# board.net
KiCad netlist of a schematic drawn in EAGLE
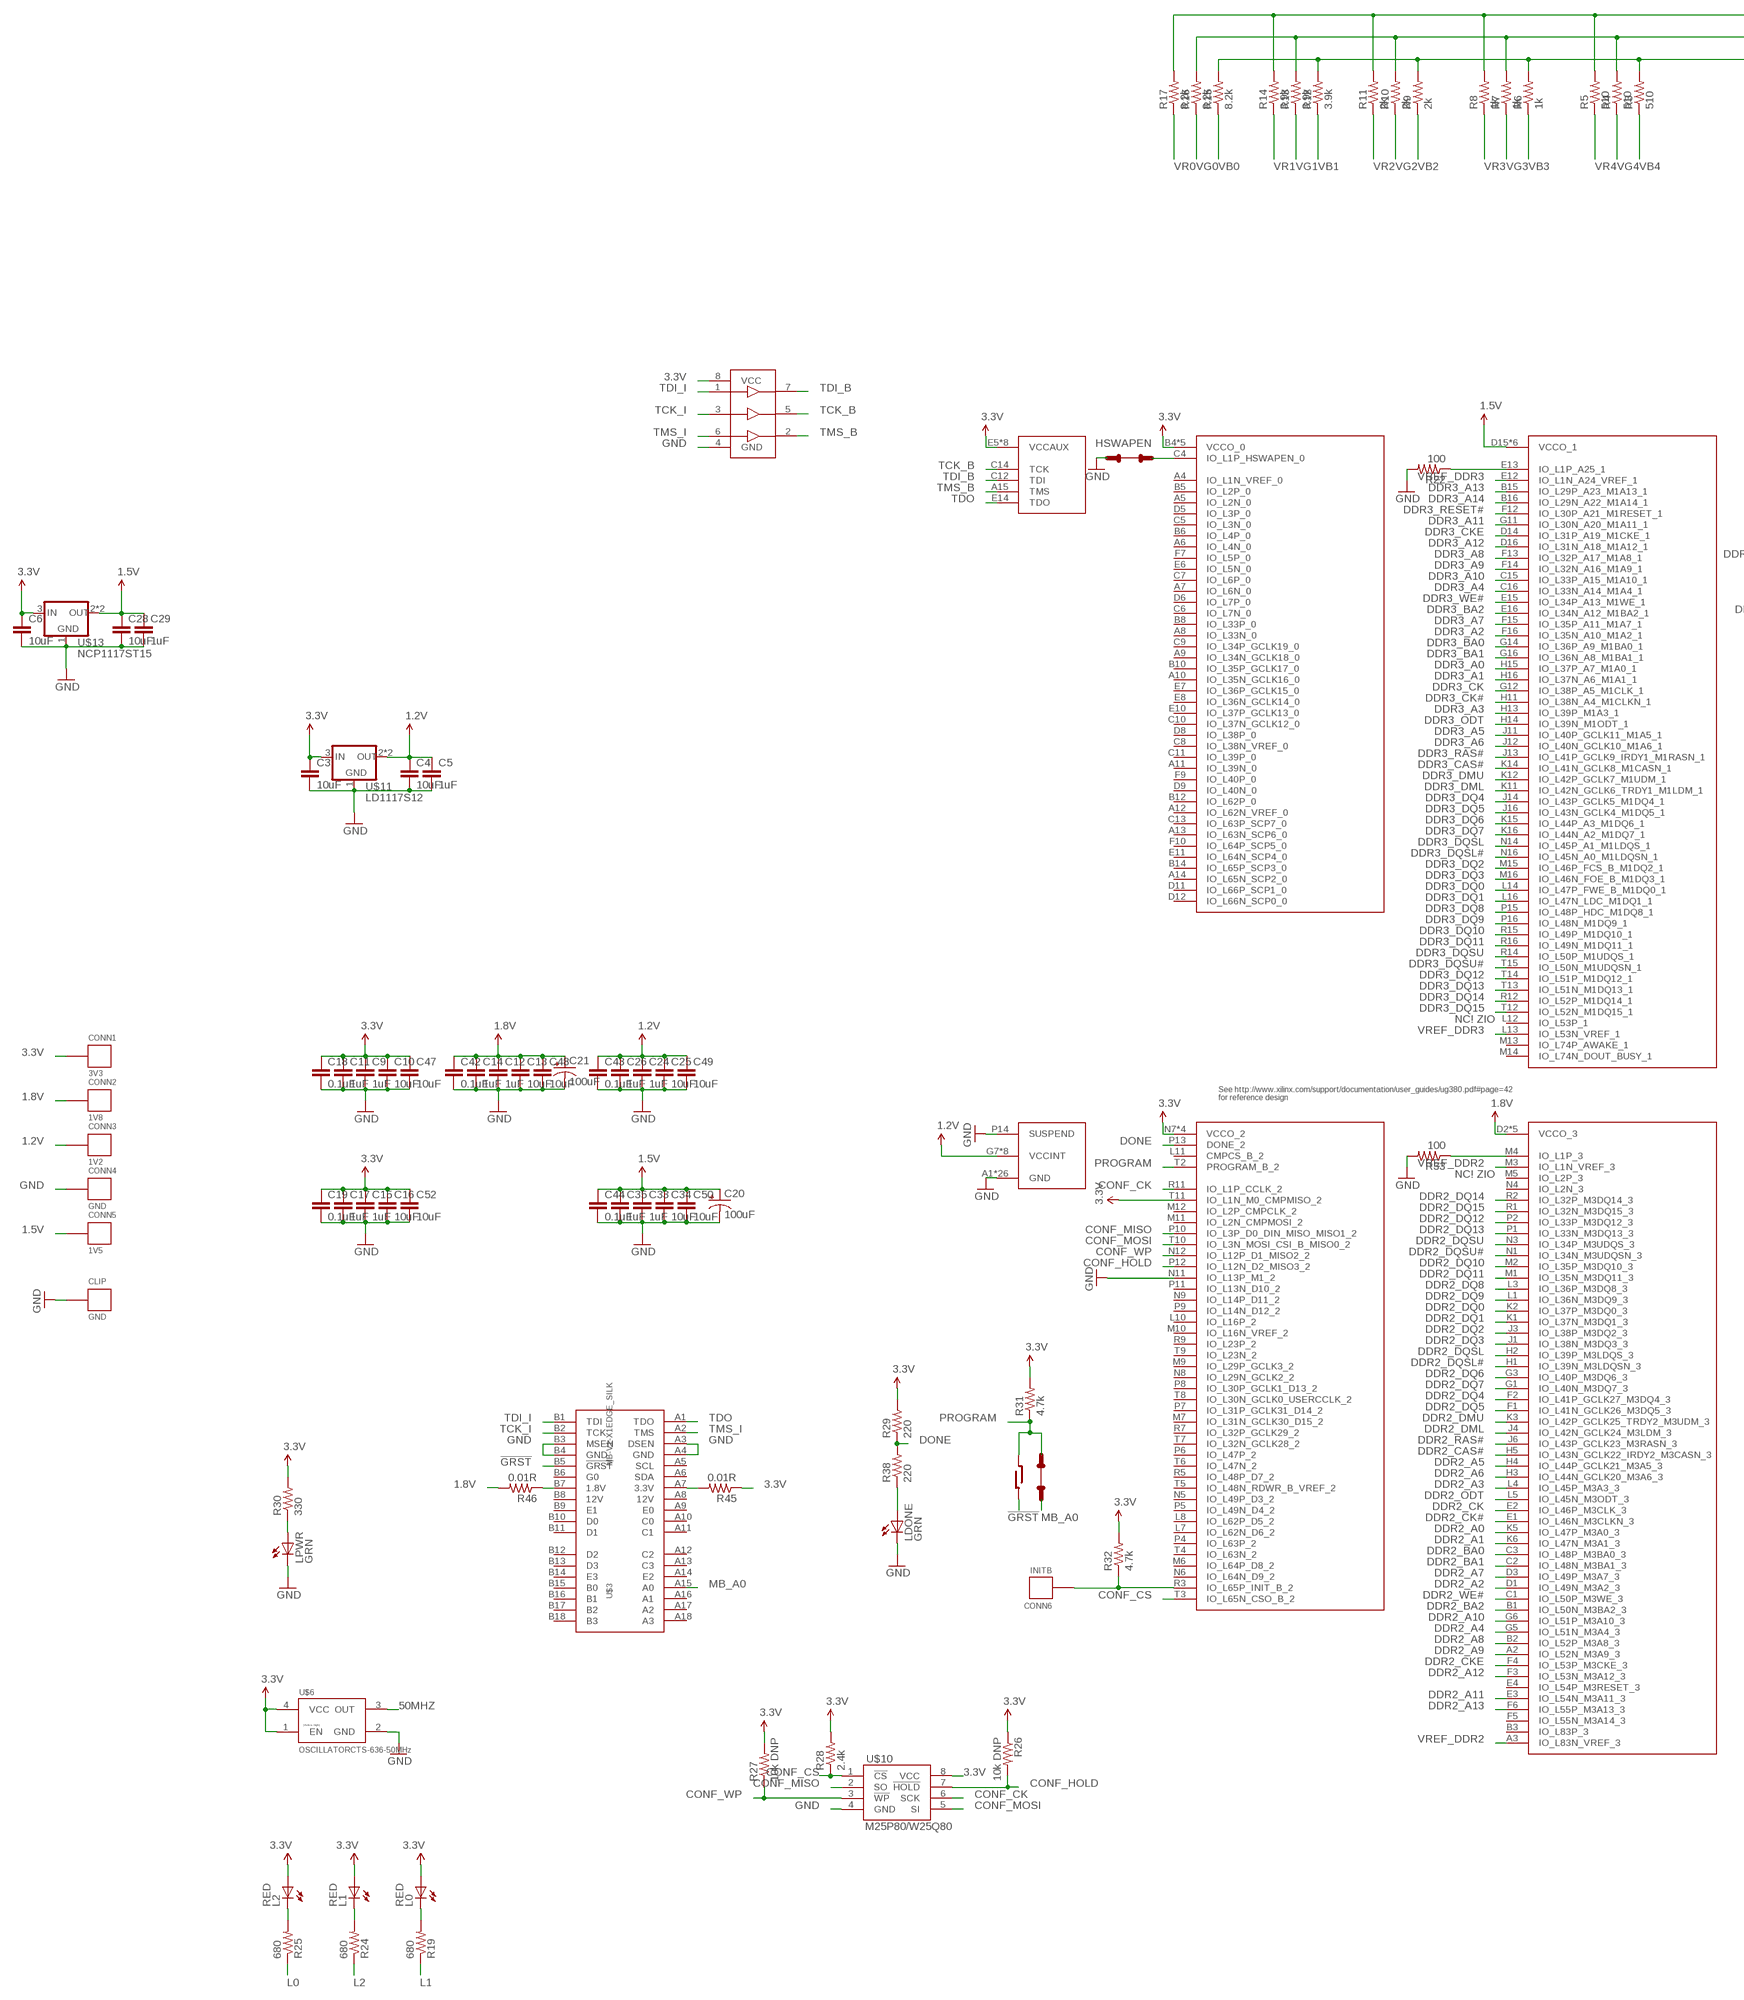
[diagram p0: schematic, sheet 1, part 1 of 2]
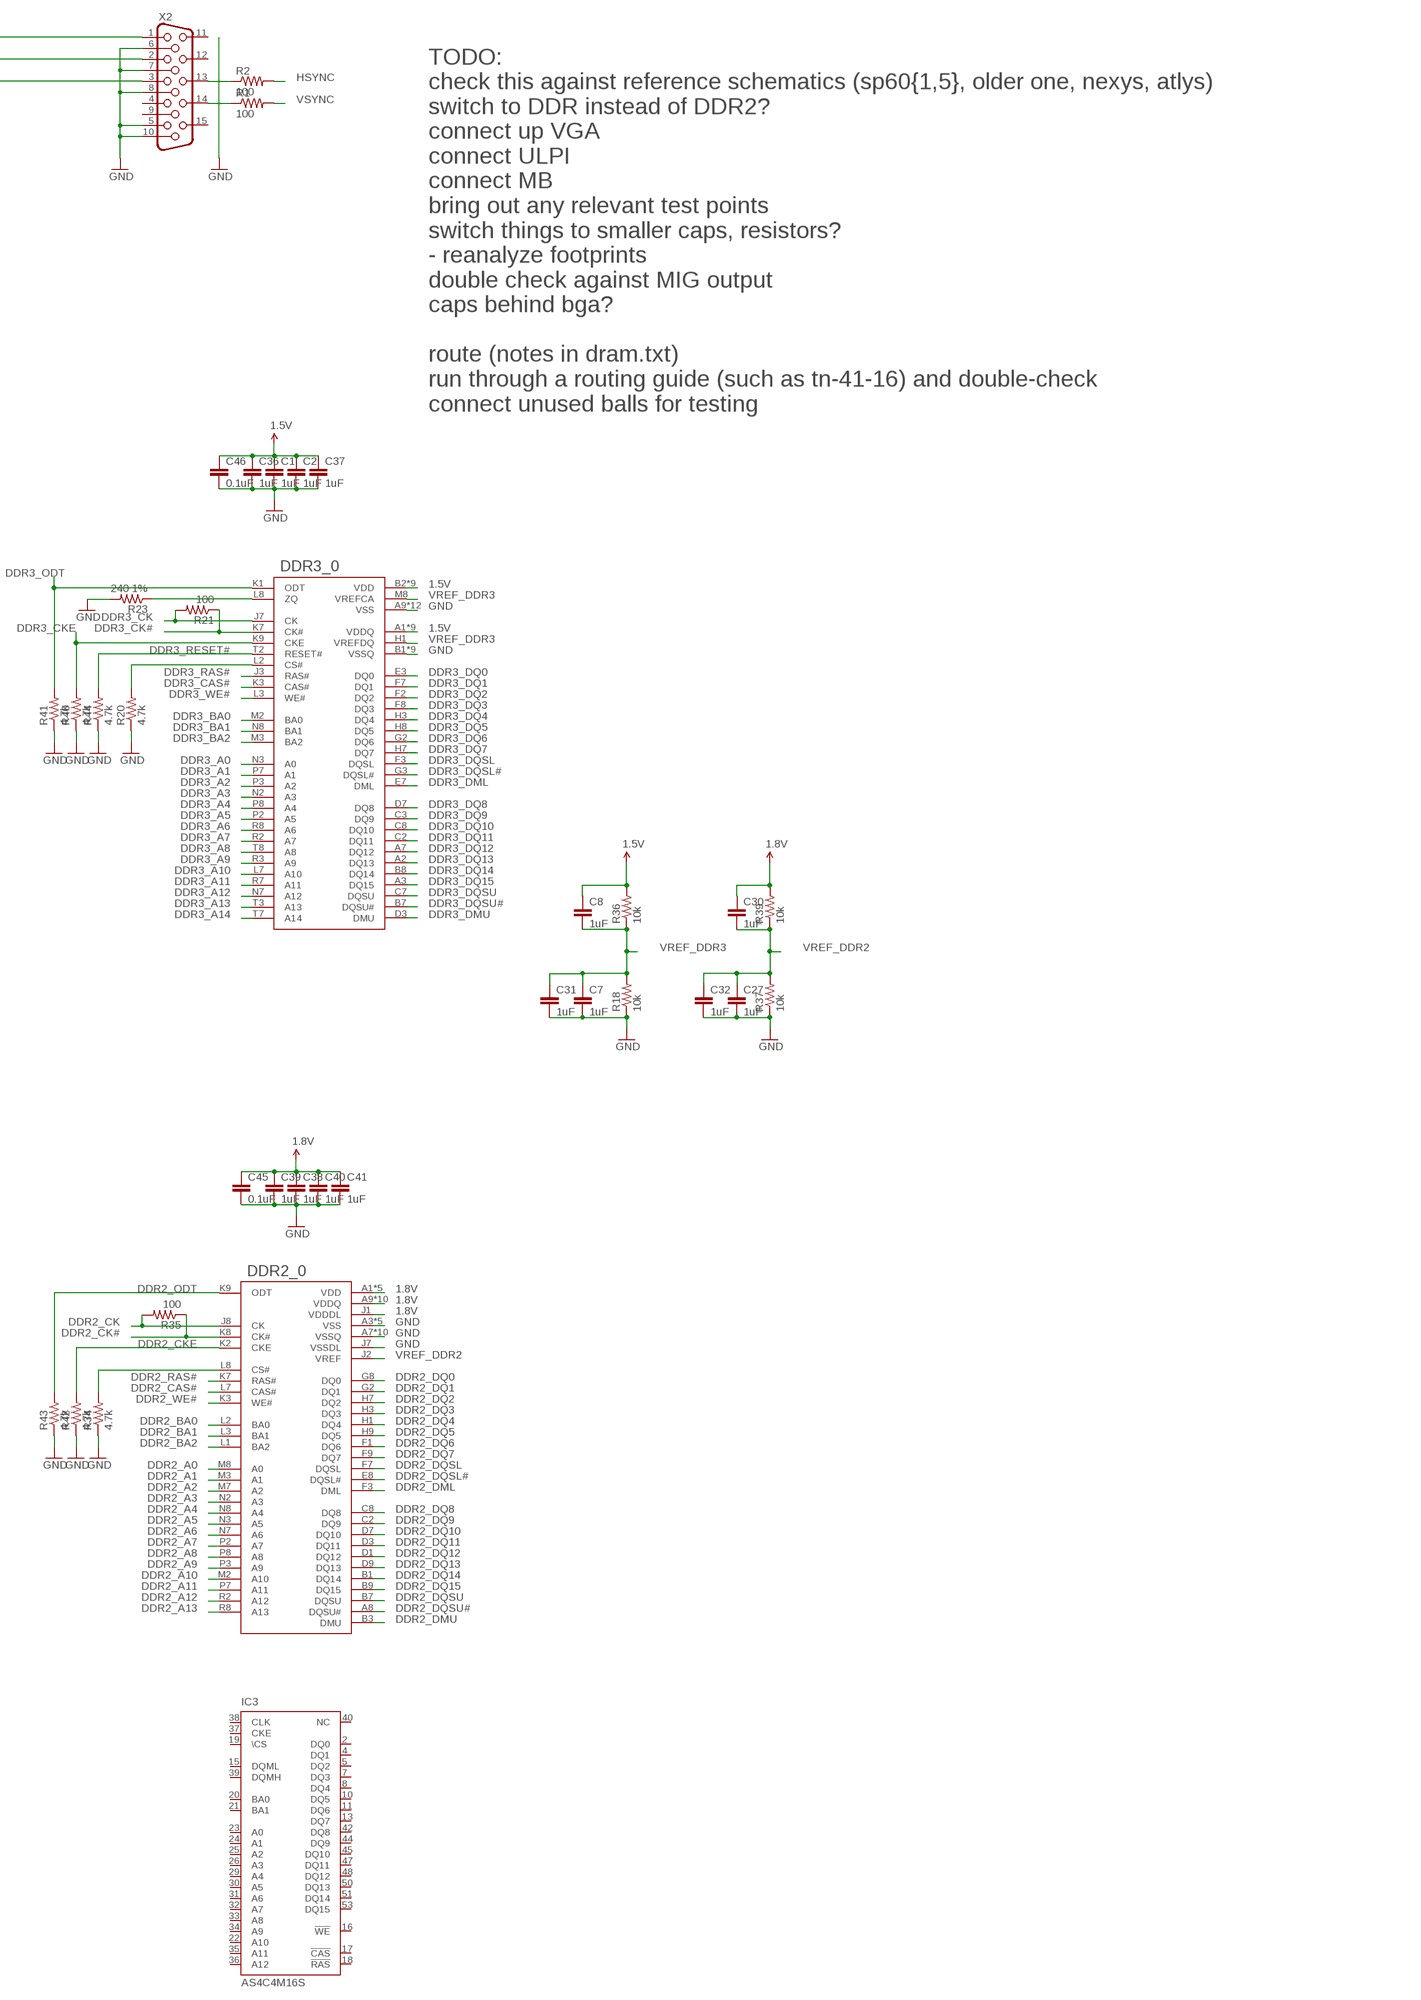
[diagram p1: schematic, sheet 1, part 2 of 2]

(export (version "E")
  (design (tool "Eeschema 10.0.6"))
  (components
    (comp (ref "C1")
      (value "1uF")
      (footprint "eagle-import:0402-CAP")
      (libsource (lib "eagle-import") (part "CAP0402-CAP"))
    )
    (comp (ref "C2")
      (value "1uF")
      (footprint "eagle-import:0402-CAP")
      (libsource (lib "eagle-import") (part "CAP0402-CAP"))
    )
    (comp (ref "C3")
      (value "10uF")
      (footprint "eagle-import:0603-CAP")
      (libsource (lib "eagle-import") (part "CAP0603"))
    )
    (comp (ref "C4")
      (value "10uF")
      (footprint "eagle-import:0603-CAP")
      (libsource (lib "eagle-import") (part "CAP0603"))
    )
    (comp (ref "C5")
      (value "1uF")
      (footprint "eagle-import:0402-CAP")
      (libsource (lib "eagle-import") (part "CAP0402-CAP"))
    )
    (comp (ref "C6")
      (value "10uF")
      (footprint "eagle-import:0603-CAP")
      (libsource (lib "eagle-import") (part "CAP0603"))
    )
    (comp (ref "C7")
      (value "1uF")
      (footprint "eagle-import:0402-CAP")
      (libsource (lib "eagle-import") (part "CAP0402-CAP"))
    )
    (comp (ref "C8")
      (value "1uF")
      (footprint "eagle-import:0402-CAP")
      (libsource (lib "eagle-import") (part "CAP0402-CAP"))
    )
    (comp (ref "C9")
      (value "1uF")
      (footprint "eagle-import:0402-CAP")
      (libsource (lib "eagle-import") (part "CAP0402-CAP"))
    )
    (comp (ref "C10")
      (value "10uF")
      (footprint "eagle-import:0603-CAP")
      (libsource (lib "eagle-import") (part "CAP0603"))
    )
    (comp (ref "C11")
      (value "1uF")
      (footprint "eagle-import:0402-CAP")
      (libsource (lib "eagle-import") (part "CAP0402-CAP"))
    )
    (comp (ref "C12")
      (value "1uF")
      (footprint "eagle-import:0402-CAP")
      (libsource (lib "eagle-import") (part "CAP0402-CAP"))
    )
    (comp (ref "C13")
      (value "10uF")
      (footprint "eagle-import:0603-CAP")
      (libsource (lib "eagle-import") (part "CAP0603"))
    )
    (comp (ref "C14")
      (value "1uF")
      (footprint "eagle-import:0402-CAP")
      (libsource (lib "eagle-import") (part "CAP0402-CAP"))
    )
    (comp (ref "C15")
      (value "1uF")
      (footprint "eagle-import:0402-CAP")
      (libsource (lib "eagle-import") (part "CAP0402-CAP"))
    )
    (comp (ref "C16")
      (value "10uF")
      (footprint "eagle-import:0603-CAP")
      (libsource (lib "eagle-import") (part "CAP0603"))
    )
    (comp (ref "C17")
      (value "1uF")
      (footprint "eagle-import:0402-CAP")
      (libsource (lib "eagle-import") (part "CAP0402-CAP"))
    )
    (comp (ref "C18")
      (value "0.1uF")
      (footprint "eagle-import:C0201")
      (libsource (lib "eagle-import") (part "CAP0201"))
    )
    (comp (ref "C19")
      (value "0.1uF")
      (footprint "eagle-import:C0201")
      (libsource (lib "eagle-import") (part "CAP0201"))
    )
    (comp (ref "C20")
      (value "100uF")
      (footprint "eagle-import:CAP-5-2")
      (libsource (lib "eagle-import") (part "CAP_POLPTH-5-2"))
    )
    (comp (ref "C21")
      (value "100uF")
      (footprint "eagle-import:CAP-5-2")
      (libsource (lib "eagle-import") (part "CAP_POLPTH-5-2"))
    )
    (comp (ref "C24")
      (value "1uF")
      (footprint "eagle-import:0402-CAP")
      (libsource (lib "eagle-import") (part "CAP0402-CAP"))
    )
    (comp (ref "C25")
      (value "10uF")
      (footprint "eagle-import:0603-CAP")
      (libsource (lib "eagle-import") (part "CAP0603"))
    )
    (comp (ref "C26")
      (value "1uF")
      (footprint "eagle-import:0402-CAP")
      (libsource (lib "eagle-import") (part "CAP0402-CAP"))
    )
    (comp (ref "C27")
      (value "1uF")
      (footprint "eagle-import:0402-CAP")
      (libsource (lib "eagle-import") (part "CAP0402-CAP"))
    )
    (comp (ref "C28")
      (value "10uF")
      (footprint "eagle-import:0603-CAP")
      (libsource (lib "eagle-import") (part "CAP0603"))
    )
    (comp (ref "C29")
      (value "1uF")
      (footprint "eagle-import:0402-CAP")
      (libsource (lib "eagle-import") (part "CAP0402-CAP"))
    )
    (comp (ref "C30")
      (value "1uF")
      (footprint "eagle-import:0402-CAP")
      (libsource (lib "eagle-import") (part "CAP0402-CAP"))
    )
    (comp (ref "C31")
      (value "1uF")
      (footprint "eagle-import:0402-CAP")
      (libsource (lib "eagle-import") (part "CAP0402-CAP"))
    )
    (comp (ref "C32")
      (value "1uF")
      (footprint "eagle-import:0402-CAP")
      (libsource (lib "eagle-import") (part "CAP0402-CAP"))
    )
    (comp (ref "C33")
      (value "1uF")
      (footprint "eagle-import:0402-CAP")
      (libsource (lib "eagle-import") (part "CAP0402-CAP"))
    )
    (comp (ref "C34")
      (value "10uF")
      (footprint "eagle-import:0603-CAP")
      (libsource (lib "eagle-import") (part "CAP0603"))
    )
    (comp (ref "C35")
      (value "1uF")
      (footprint "eagle-import:0402-CAP")
      (libsource (lib "eagle-import") (part "CAP0402-CAP"))
    )
    (comp (ref "C36")
      (value "1uF")
      (footprint "eagle-import:0402-CAP")
      (libsource (lib "eagle-import") (part "CAP0402-CAP"))
    )
    (comp (ref "C37")
      (value "1uF")
      (footprint "eagle-import:0402-CAP")
      (libsource (lib "eagle-import") (part "CAP0402-CAP"))
    )
    (comp (ref "C38")
      (value "1uF")
      (footprint "eagle-import:0402-CAP")
      (libsource (lib "eagle-import") (part "CAP0402-CAP"))
    )
    (comp (ref "C39")
      (value "1uF")
      (footprint "eagle-import:0402-CAP")
      (libsource (lib "eagle-import") (part "CAP0402-CAP"))
    )
    (comp (ref "C40")
      (value "1uF")
      (footprint "eagle-import:0402-CAP")
      (libsource (lib "eagle-import") (part "CAP0402-CAP"))
    )
    (comp (ref "C41")
      (value "1uF")
      (footprint "eagle-import:0402-CAP")
      (libsource (lib "eagle-import") (part "CAP0402-CAP"))
    )
    (comp (ref "C42")
      (value "0.1uF")
      (footprint "eagle-import:C0201")
      (libsource (lib "eagle-import") (part "CAP0201"))
    )
    (comp (ref "C43")
      (value "0.1uF")
      (footprint "eagle-import:C0201")
      (libsource (lib "eagle-import") (part "CAP0201"))
    )
    (comp (ref "C44")
      (value "0.1uF")
      (footprint "eagle-import:C0201")
      (libsource (lib "eagle-import") (part "CAP0201"))
    )
    (comp (ref "C45")
      (value "0.1uF")
      (footprint "eagle-import:C0201")
      (libsource (lib "eagle-import") (part "CAP0201"))
    )
    (comp (ref "C46")
      (value "0.1uF")
      (footprint "eagle-import:C0201")
      (libsource (lib "eagle-import") (part "CAP0201"))
    )
    (comp (ref "C47")
      (value "10uF")
      (footprint "eagle-import:0603-CAP")
      (libsource (lib "eagle-import") (part "CAP0603"))
    )
    (comp (ref "C48")
      (value "10uF")
      (footprint "eagle-import:0603-CAP")
      (libsource (lib "eagle-import") (part "CAP0603"))
    )
    (comp (ref "C49")
      (value "10uF")
      (footprint "eagle-import:0603-CAP")
      (libsource (lib "eagle-import") (part "CAP0603"))
    )
    (comp (ref "C50")
      (value "10uF")
      (footprint "eagle-import:0603-CAP")
      (libsource (lib "eagle-import") (part "CAP0603"))
    )
    (comp (ref "C52")
      (value "10uF")
      (footprint "eagle-import:0603-CAP")
      (libsource (lib "eagle-import") (part "CAP0603"))
    )
    (comp (ref "CLIP")
      (value "GND")
      (footprint "eagle-import:CLIP-AREA")
      (libsource (lib "eagle-import") (part "CONNECTORCLIP"))
    )
    (comp (ref "CONN1")
      (value "3V3")
      (footprint "eagle-import:HOLE_22AWG")
      (libsource (lib "eagle-import") (part "CONNECTOR22AWG"))
    )
    (comp (ref "CONN2")
      (value "1V8")
      (footprint "eagle-import:HOLE_22AWG")
      (libsource (lib "eagle-import") (part "CONNECTOR22AWG"))
    )
    (comp (ref "CONN3")
      (value "1V2")
      (footprint "eagle-import:HOLE_22AWG")
      (libsource (lib "eagle-import") (part "CONNECTOR22AWG"))
    )
    (comp (ref "CONN4")
      (value "GND")
      (footprint "eagle-import:HOLE_22AWG")
      (libsource (lib "eagle-import") (part "CONNECTOR22AWG"))
    )
    (comp (ref "CONN5")
      (value "1V5")
      (footprint "eagle-import:HOLE_22AWG")
      (libsource (lib "eagle-import") (part "CONNECTOR22AWG"))
    )
    (comp (ref "CONN6")
      (value "INITB")
      (footprint "eagle-import:TESTPAD-1.27")
      (libsource (lib "eagle-import") (part "CONNECTOR1.27"))
    )
    (comp (ref "DDR2_0")
      (value "DDR2X16")
      (footprint "eagle-import:BGA84")
      (libsource (lib "eagle-import") (part "DDR2X16"))
    )
    (comp (ref "DDR3_0")
      (value "DDR3X16")
      (footprint "eagle-import:BGA96")
      (libsource (lib "eagle-import") (part "DDR3X16"))
    )
    (comp (ref "IC1")
      (value "XC6S{9,16,25}LX-FT256")
      (footprint "eagle-import:XILINX_FT256")
      (libsource (lib "eagle-import") (part "XC6S{9,16,25}LX-FT256"))
    )
    (comp (ref "IC2")
      (value "74X3G34")
      (footprint "eagle-import:TSSOP8")
      (libsource (lib "eagle-import") (part "74X3G34"))
    )
    (comp (ref "IC3")
      (value "AS4C4M16S")
      (footprint "eagle-import:TSOP54-400")
      (libsource (lib "eagle-import") (part "MT48LC64M4A2"))
    )
    (comp (ref "L0")
      (value "RED")
      (footprint "eagle-import:0603_LED")
      (libsource (lib "eagle-import") (part "LED0603"))
    )
    (comp (ref "L1")
      (value "RED")
      (footprint "eagle-import:0603_LED")
      (libsource (lib "eagle-import") (part "LED0603"))
    )
    (comp (ref "L2")
      (value "RED")
      (footprint "eagle-import:0603_LED")
      (libsource (lib "eagle-import") (part "LED0603"))
    )
    (comp (ref "LDONE")
      (value "GRN")
      (footprint "eagle-import:0603_LED")
      (libsource (lib "eagle-import") (part "LED0603"))
    )
    (comp (ref "LPWR")
      (value "GRN")
      (footprint "eagle-import:0603_LED")
      (libsource (lib "eagle-import") (part "LED0603"))
    )
    (comp (ref "R1")
      (value "100")
      (footprint "eagle-import:0603-RES")
      (libsource (lib "eagle-import") (part "RESISTOR0603"))
    )
    (comp (ref "R2")
      (value "100")
      (footprint "eagle-import:0603-RES")
      (libsource (lib "eagle-import") (part "RESISTOR0603"))
    )
    (comp (ref "R3")
      (value "510")
      (footprint "eagle-import:0603-RES")
      (libsource (lib "eagle-import") (part "RESISTOR0603"))
    )
    (comp (ref "R4")
      (value "510")
      (footprint "eagle-import:0603-RES")
      (libsource (lib "eagle-import") (part "RESISTOR0603"))
    )
    (comp (ref "R5")
      (value "510")
      (footprint "eagle-import:0603-RES")
      (libsource (lib "eagle-import") (part "RESISTOR0603"))
    )
    (comp (ref "R6")
      (value "1k")
      (footprint "eagle-import:0603-RES")
      (libsource (lib "eagle-import") (part "RESISTOR0603"))
    )
    (comp (ref "R7")
      (value "1k")
      (footprint "eagle-import:0603-RES")
      (libsource (lib "eagle-import") (part "RESISTOR0603"))
    )
    (comp (ref "R8")
      (value "1k")
      (footprint "eagle-import:0603-RES")
      (libsource (lib "eagle-import") (part "RESISTOR0603"))
    )
    (comp (ref "R9")
      (value "2k")
      (footprint "eagle-import:0603-RES")
      (libsource (lib "eagle-import") (part "RESISTOR0603"))
    )
    (comp (ref "R10")
      (value "2k")
      (footprint "eagle-import:0603-RES")
      (libsource (lib "eagle-import") (part "RESISTOR0603"))
    )
    (comp (ref "R11")
      (value "2k")
      (footprint "eagle-import:0603-RES")
      (libsource (lib "eagle-import") (part "RESISTOR0603"))
    )
    (comp (ref "R12")
      (value "3.9k")
      (footprint "eagle-import:0603-RES")
      (libsource (lib "eagle-import") (part "RESISTOR0603"))
    )
    (comp (ref "R13")
      (value "3.9k")
      (footprint "eagle-import:0603-RES")
      (libsource (lib "eagle-import") (part "RESISTOR0603"))
    )
    (comp (ref "R14")
      (value "3.9k")
      (footprint "eagle-import:0603-RES")
      (libsource (lib "eagle-import") (part "RESISTOR0603"))
    )
    (comp (ref "R15")
      (value "8.2k")
      (footprint "eagle-import:0603-RES")
      (libsource (lib "eagle-import") (part "RESISTOR0603"))
    )
    (comp (ref "R16")
      (value "8.2k")
      (footprint "eagle-import:0603-RES")
      (libsource (lib "eagle-import") (part "RESISTOR0603"))
    )
    (comp (ref "R17")
      (value "8.2k")
      (footprint "eagle-import:0603-RES")
      (libsource (lib "eagle-import") (part "RESISTOR0603"))
    )
    (comp (ref "R18")
      (value "10k")
      (footprint "eagle-import:0603-RES")
      (libsource (lib "eagle-import") (part "RESISTOR0603"))
    )
    (comp (ref "R19")
      (value "680")
      (footprint "eagle-import:0603-RES")
      (libsource (lib "eagle-import") (part "RESISTOR0603"))
    )
    (comp (ref "R20")
      (value "4.7k")
      (footprint "eagle-import:0402-RES")
      (libsource (lib "eagle-import") (part "RESISTOR0402"))
    )
    (comp (ref "R21")
      (value "100")
      (footprint "eagle-import:0603-RES")
      (libsource (lib "eagle-import") (part "RESISTOR0603"))
    )
    (comp (ref "R22")
      (value "100")
      (footprint "eagle-import:0603-RES")
      (libsource (lib "eagle-import") (part "RESISTOR0603"))
    )
    (comp (ref "R23")
      (value "240 1%")
      (footprint "eagle-import:0603-RES")
      (libsource (lib "eagle-import") (part "RESISTOR0603"))
    )
    (comp (ref "R24")
      (value "680")
      (footprint "eagle-import:0603-RES")
      (libsource (lib "eagle-import") (part "RESISTOR0603"))
    )
    (comp (ref "R25")
      (value "680")
      (footprint "eagle-import:0603-RES")
      (libsource (lib "eagle-import") (part "RESISTOR0603"))
    )
    (comp (ref "R26")
      (value "10k DNP")
      (footprint "eagle-import:0402-RES")
      (libsource (lib "eagle-import") (part "RESISTOR0402"))
    )
    (comp (ref "R27")
      (value "10k DNP")
      (footprint "eagle-import:0402-RES")
      (libsource (lib "eagle-import") (part "RESISTOR0402"))
    )
    (comp (ref "R28")
      (value "2.4k")
      (footprint "eagle-import:0603-RES")
      (libsource (lib "eagle-import") (part "RESISTOR0603"))
    )
    (comp (ref "R29")
      (value "220")
      (footprint "eagle-import:0603-RES")
      (libsource (lib "eagle-import") (part "RESISTOR0603"))
    )
    (comp (ref "R30")
      (value "330")
      (footprint "eagle-import:0603-RES")
      (libsource (lib "eagle-import") (part "RESISTOR0603"))
    )
    (comp (ref "R31")
      (value "4.7k")
      (footprint "eagle-import:0603-RES")
      (libsource (lib "eagle-import") (part "RESISTOR0603"))
    )
    (comp (ref "R32")
      (value "4.7k")
      (footprint "eagle-import:0603-RES")
      (libsource (lib "eagle-import") (part "RESISTOR0603"))
    )
    (comp (ref "R33")
      (value "100")
      (footprint "eagle-import:0603-RES")
      (libsource (lib "eagle-import") (part "RESISTOR0603"))
    )
    (comp (ref "R34")
      (value "4.7k")
      (footprint "eagle-import:0402-RES")
      (libsource (lib "eagle-import") (part "RESISTOR0402"))
    )
    (comp (ref "R35")
      (value "100")
      (footprint "eagle-import:0603-RES")
      (libsource (lib "eagle-import") (part "RESISTOR0603"))
    )
    (comp (ref "R36")
      (value "10k")
      (footprint "eagle-import:0603-RES")
      (libsource (lib "eagle-import") (part "RESISTOR0603"))
    )
    (comp (ref "R37")
      (value "10k")
      (footprint "eagle-import:0603-RES")
      (libsource (lib "eagle-import") (part "RESISTOR0603"))
    )
    (comp (ref "R38")
      (value "220")
      (footprint "eagle-import:0603-RES")
      (libsource (lib "eagle-import") (part "RESISTOR0603"))
    )
    (comp (ref "R39")
      (value "10k")
      (footprint "eagle-import:0603-RES")
      (libsource (lib "eagle-import") (part "RESISTOR0603"))
    )
    (comp (ref "R40")
      (value "4.7k")
      (footprint "eagle-import:0402-RES")
      (libsource (lib "eagle-import") (part "RESISTOR0402"))
    )
    (comp (ref "R41")
      (value "4.7k")
      (footprint "eagle-import:0402-RES")
      (libsource (lib "eagle-import") (part "RESISTOR0402"))
    )
    (comp (ref "R42")
      (value "4.7k")
      (footprint "eagle-import:0402-RES")
      (libsource (lib "eagle-import") (part "RESISTOR0402"))
    )
    (comp (ref "R43")
      (value "4.7k")
      (footprint "eagle-import:0402-RES")
      (libsource (lib "eagle-import") (part "RESISTOR0402"))
    )
    (comp (ref "R44")
      (value "4.7k")
      (footprint "eagle-import:0402-RES")
      (libsource (lib "eagle-import") (part "RESISTOR0402"))
    )
    (comp (ref "R45")
      (value "0.01R")
      (footprint "eagle-import:0603-RES")
      (libsource (lib "eagle-import") (part "RESISTOR0603"))
    )
    (comp (ref "R46")
      (value "0.01R")
      (footprint "eagle-import:0603-RES")
      (libsource (lib "eagle-import") (part "RESISTOR0603"))
    )
    (comp (ref "SB1")
      (value "SOLDER-BRIDGEOPEN")
      (footprint "eagle-import:SOLDER-BRIDGE-OPEN")
      (libsource (lib "eagle-import") (part "SOLDER-BRIDGEOPEN"))
    )
    (comp (ref "SB2")
      (value "TRACE-CUT")
      (footprint "eagle-import:TRACE-CUT")
      (libsource (lib "eagle-import") (part "TRACE-CUT"))
    )
    (comp (ref "SB5")
      (value "TRACE-CUT")
      (footprint "eagle-import:TRACE-CUT")
      (libsource (lib "eagle-import") (part "TRACE-CUT"))
    )
    (comp (ref "U$3")
      (value "MB-V1-X1EDGE_SILK")
      (footprint "eagle-import:MB-V1-X1-EDGE")
      (libsource (lib "eagle-import") (part "MB-V1-X1EDGE_SILK"))
    )
    (comp (ref "U$6")
      (value "OSCILLATORCTS-636-50MHz")
      (footprint "eagle-import:CTS-636")
      (libsource (lib "eagle-import") (part "OSCILLATORCTS-636"))
    )
    (comp (ref "U$10")
      (value "M25P80/W25Q80")
      (footprint "eagle-import:SO08")
      (libsource (lib "eagle-import") (part "S25FL"))
    )
    (comp (ref "U$11")
      (value "LD1117S12")
      (footprint "eagle-import:SOT223")
      (libsource (lib "eagle-import") (part "VREGSOT223"))
    )
    (comp (ref "U$13")
      (value "NCP1117ST15")
      (footprint "eagle-import:SOT223")
      (libsource (lib "eagle-import") (part "VREGSOT223"))
    )
    (comp (ref "X2")
      (value "HF15H")
      (footprint "eagle-import:HDF15H")
      (libsource (lib "eagle-import") (part "HF15H"))
    )
  )
  (nets
    (net (code "1") (name "/50MHZ") (class "Default")
      (node (ref "U$6") (pin "3") (pinfunction "OUT_3") (pintype "bidirectional"))
    )
    (net (code "2") (name "/CONF_CK") (class "Default")
      (node (ref "IC1") (pin "R11") (pinfunction "IO_L1P_CCLK_2_R11") (pintype "bidirectional"))
      (node (ref "U$10") (pin "6") (pinfunction "SCK_6") (pintype "bidirectional"))
    )
    (net (code "3") (name "/CONF_CS") (class "Default")
      (node (ref "IC1") (pin "T3") (pinfunction "IO_L65N_CSO_B_2_T3") (pintype "bidirectional"))
      (node (ref "R28") (pin "1") (pinfunction "1_1") (pintype "passive"))
      (node (ref "U$10") (pin "1") (pinfunction "~{CS}_1") (pintype "bidirectional"))
    )
    (net (code "4") (name "/CONF_HOLD") (class "Default")
      (node (ref "IC1") (pin "P12") (pinfunction "IO_L12N_D2_MISO3_2_P12") (pintype "bidirectional"))
      (node (ref "R26") (pin "2") (pinfunction "2_2") (pintype "passive"))
      (node (ref "U$10") (pin "7") (pinfunction "~{HOLD}_7") (pintype "bidirectional"))
    )
    (net (code "5") (name "/CONF_MISO") (class "Default")
      (node (ref "IC1") (pin "P10") (pinfunction "IO_L3P_D0_DIN_MISO_MISO1_2_P10") (pintype "bidirectional"))
      (node (ref "U$10") (pin "2") (pinfunction "SO_2") (pintype "bidirectional"))
    )
    (net (code "6") (name "/CONF_MOSI") (class "Default")
      (node (ref "IC1") (pin "T10") (pinfunction "IO_L3N_MOSI_CSI_B_MISO0_2_T10") (pintype "bidirectional"))
      (node (ref "U$10") (pin "5") (pinfunction "SI_5") (pintype "bidirectional"))
    )
    (net (code "7") (name "/CONF_WP") (class "Default")
      (node (ref "IC1") (pin "N12") (pinfunction "IO_L12P_D1_MISO2_2_N12") (pintype "bidirectional"))
      (node (ref "R27") (pin "1") (pinfunction "1_1") (pintype "passive"))
      (node (ref "U$10") (pin "3") (pinfunction "~{WP}_3") (pintype "bidirectional"))
    )
    (net (code "8") (name "/DDR2_A0") (class "Default")
      (node (ref "DDR2_0") (pin "M8") (pinfunction "A0_M8") (pintype "input"))
      (node (ref "IC1") (pin "K5") (pinfunction "IO_L47P_M3A0_3_K5") (pintype "bidirectional"))
    )
    (net (code "9") (name "/DDR2_A1") (class "Default")
      (node (ref "DDR2_0") (pin "M3") (pinfunction "A1_M3") (pintype "input"))
      (node (ref "IC1") (pin "K6") (pinfunction "IO_L47N_M3A1_3_K6") (pintype "bidirectional"))
    )
    (net (code "10") (name "/DDR2_A2") (class "Default")
      (node (ref "DDR2_0") (pin "M7") (pinfunction "A2_M7") (pintype "input"))
      (node (ref "IC1") (pin "D1") (pinfunction "IO_L49N_M3A2_3_D1") (pintype "bidirectional"))
    )
    (net (code "11") (name "/DDR2_A3") (class "Default")
      (node (ref "DDR2_0") (pin "N2") (pinfunction "A3_N2") (pintype "input"))
      (node (ref "IC1") (pin "L4") (pinfunction "IO_L45P_M3A3_3_L4") (pintype "bidirectional"))
    )
    (net (code "12") (name "/DDR2_A4") (class "Default")
      (node (ref "DDR2_0") (pin "N8") (pinfunction "A4_N8") (pintype "input"))
      (node (ref "IC1") (pin "G5") (pinfunction "IO_L51N_M3A4_3_G5") (pintype "bidirectional"))
    )
    (net (code "13") (name "/DDR2_A5") (class "Default")
      (node (ref "DDR2_0") (pin "N3") (pinfunction "A5_N3") (pintype "input"))
      (node (ref "IC1") (pin "H4") (pinfunction "IO_L44P_GCLK21_M3A5_3_H4") (pintype "bidirectional"))
    )
    (net (code "14") (name "/DDR2_A6") (class "Default")
      (node (ref "DDR2_0") (pin "N7") (pinfunction "A6_N7") (pintype "input"))
      (node (ref "IC1") (pin "H3") (pinfunction "IO_L44N_GCLK20_M3A6_3_H3") (pintype "bidirectional"))
    )
    (net (code "15") (name "/DDR2_A7") (class "Default")
      (node (ref "DDR2_0") (pin "P2") (pinfunction "A7_P2") (pintype "input"))
      (node (ref "IC1") (pin "D3") (pinfunction "IO_L49P_M3A7_3_D3") (pintype "bidirectional"))
    )
    (net (code "16") (name "/DDR2_A8") (class "Default")
      (node (ref "DDR2_0") (pin "P8") (pinfunction "A8_P8") (pintype "input"))
      (node (ref "IC1") (pin "B2") (pinfunction "IO_L52P_M3A8_3_B2") (pintype "bidirectional"))
    )
    (net (code "17") (name "/DDR2_A9") (class "Default")
      (node (ref "DDR2_0") (pin "P3") (pinfunction "A9_P3") (pintype "input"))
      (node (ref "IC1") (pin "A2") (pinfunction "IO_L52N_M3A9_3_A2") (pintype "bidirectional"))
    )
    (net (code "18") (name "/DDR2_A10") (class "Default")
      (node (ref "DDR2_0") (pin "M2") (pinfunction "A10_M2") (pintype "input"))
      (node (ref "IC1") (pin "G6") (pinfunction "IO_L51P_M3A10_3_G6") (pintype "bidirectional"))
    )
    (net (code "19") (name "/DDR2_A11") (class "Default")
      (node (ref "DDR2_0") (pin "P7") (pinfunction "A11_P7") (pintype "input"))
      (node (ref "IC1") (pin "E3") (pinfunction "IO_L54N_M3A11_3_E3") (pintype "bidirectional"))
    )
    (net (code "20") (name "/DDR2_A12") (class "Default")
      (node (ref "DDR2_0") (pin "R2") (pinfunction "A12_R2") (pintype "input"))
      (node (ref "IC1") (pin "F3") (pinfunction "IO_L53N_M3A12_3_F3") (pintype "bidirectional"))
    )
    (net (code "21") (name "/DDR2_A13") (class "Default")
      (node (ref "DDR2_0") (pin "R8") (pinfunction "A13_R8") (pintype "input"))
      (node (ref "IC1") (pin "F6") (pinfunction "IO_L55P_M3A13_3_F6") (pintype "bidirectional"))
    )
    (net (code "22") (name "/DDR2_BA0") (class "Default")
      (node (ref "DDR2_0") (pin "L2") (pinfunction "BA0_L2") (pintype "input"))
      (node (ref "IC1") (pin "C3") (pinfunction "IO_L48P_M3BA0_3_C3") (pintype "bidirectional"))
    )
    (net (code "23") (name "/DDR2_BA1") (class "Default")
      (node (ref "DDR2_0") (pin "L3") (pinfunction "BA1_L3") (pintype "input"))
      (node (ref "IC1") (pin "C2") (pinfunction "IO_L48N_M3BA1_3_C2") (pintype "bidirectional"))
    )
    (net (code "24") (name "/DDR2_BA2") (class "Default")
      (node (ref "DDR2_0") (pin "L1") (pinfunction "BA2_L1") (pintype "input"))
      (node (ref "IC1") (pin "B1") (pinfunction "IO_L50N_M3BA2_3_B1") (pintype "bidirectional"))
    )
    (net (code "25") (name "/DDR2_CAS#") (class "Default")
      (node (ref "DDR2_0") (pin "L7") (pinfunction "CAS#_L7") (pintype "input"))
      (node (ref "IC1") (pin "H5") (pinfunction "IO_L43N_GCLK22_IRDY2_M3CASN_3_H5") (pintype "bidirectional"))
    )
    (net (code "26") (name "/DDR2_CK") (class "Default")
      (node (ref "DDR2_0") (pin "J8") (pinfunction "CK_J8") (pintype "input"))
      (node (ref "IC1") (pin "E2") (pinfunction "IO_L46P_M3CLK_3_E2") (pintype "bidirectional"))
      (node (ref "R35") (pin "2") (pinfunction "2_2") (pintype "passive"))
    )
    (net (code "27") (name "/DDR2_CK#") (class "Default")
      (node (ref "DDR2_0") (pin "K8") (pinfunction "CK#_K8") (pintype "input"))
      (node (ref "IC1") (pin "E1") (pinfunction "IO_L46N_M3CLKN_3_E1") (pintype "bidirectional"))
      (node (ref "R35") (pin "1") (pinfunction "1_1") (pintype "passive"))
    )
    (net (code "28") (name "/DDR2_CKE") (class "Default")
      (node (ref "DDR2_0") (pin "K2") (pinfunction "CKE_K2") (pintype "input"))
      (node (ref "IC1") (pin "F4") (pinfunction "IO_L53P_M3CKE_3_F4") (pintype "bidirectional"))
      (node (ref "R42") (pin "2") (pinfunction "2_2") (pintype "passive"))
    )
    (net (code "29") (name "/DDR2_DML") (class "Default")
      (node (ref "DDR2_0") (pin "F3") (pinfunction "DML_F3") (pintype "input"))
      (node (ref "IC1") (pin "J4") (pinfunction "IO_L42N_GCLK24_M3LDM_3_J4") (pintype "bidirectional"))
    )
    (net (code "30") (name "/DDR2_DMU") (class "Default")
      (node (ref "DDR2_0") (pin "B3") (pinfunction "DMU_B3") (pintype "input"))
      (node (ref "IC1") (pin "K3") (pinfunction "IO_L42P_GCLK25_TRDY2_M3UDM_3_K3") (pintype "bidirectional"))
    )
    (net (code "31") (name "/DDR2_DQ0") (class "Default")
      (node (ref "DDR2_0") (pin "G8") (pinfunction "DQ0_G8") (pintype "bidirectional"))
      (node (ref "IC1") (pin "K2") (pinfunction "IO_L37P_M3DQ0_3_K2") (pintype "bidirectional"))
    )
    (net (code "32") (name "/DDR2_DQ1") (class "Default")
      (node (ref "DDR2_0") (pin "G2") (pinfunction "DQ1_G2") (pintype "bidirectional"))
      (node (ref "IC1") (pin "K1") (pinfunction "IO_L37N_M3DQ1_3_K1") (pintype "bidirectional"))
    )
    (net (code "33") (name "/DDR2_DQ2") (class "Default")
      (node (ref "DDR2_0") (pin "H7") (pinfunction "DQ2_H7") (pintype "bidirectional"))
      (node (ref "IC1") (pin "J3") (pinfunction "IO_L38P_M3DQ2_3_J3") (pintype "bidirectional"))
    )
    (net (code "34") (name "/DDR2_DQ3") (class "Default")
      (node (ref "DDR2_0") (pin "H3") (pinfunction "DQ3_H3") (pintype "bidirectional"))
      (node (ref "IC1") (pin "J1") (pinfunction "IO_L38N_M3DQ3_3_J1") (pintype "bidirectional"))
    )
    (net (code "35") (name "/DDR2_DQ4") (class "Default")
      (node (ref "DDR2_0") (pin "H1") (pinfunction "DQ4_H1") (pintype "bidirectional"))
      (node (ref "IC1") (pin "F2") (pinfunction "IO_L41P_GCLK27_M3DQ4_3_F2") (pintype "bidirectional"))
    )
    (net (code "36") (name "/DDR2_DQ5") (class "Default")
      (node (ref "DDR2_0") (pin "H9") (pinfunction "DQ5_H9") (pintype "bidirectional"))
      (node (ref "IC1") (pin "F1") (pinfunction "IO_L41N_GCLK26_M3DQ5_3_F1") (pintype "bidirectional"))
    )
    (net (code "37") (name "/DDR2_DQ6") (class "Default")
      (node (ref "DDR2_0") (pin "F1") (pinfunction "DQ6_F1") (pintype "bidirectional"))
      (node (ref "IC1") (pin "G3") (pinfunction "IO_L40P_M3DQ6_3_G3") (pintype "bidirectional"))
    )
    (net (code "38") (name "/DDR2_DQ7") (class "Default")
      (node (ref "DDR2_0") (pin "F9") (pinfunction "DQ7_F9") (pintype "bidirectional"))
      (node (ref "IC1") (pin "G1") (pinfunction "IO_L40N_M3DQ7_3_G1") (pintype "bidirectional"))
    )
    (net (code "39") (name "/DDR2_DQ8") (class "Default")
      (node (ref "DDR2_0") (pin "C8") (pinfunction "DQ8_C8") (pintype "bidirectional"))
      (node (ref "IC1") (pin "L3") (pinfunction "IO_L36P_M3DQ8_3_L3") (pintype "bidirectional"))
    )
    (net (code "40") (name "/DDR2_DQ9") (class "Default")
      (node (ref "DDR2_0") (pin "C2") (pinfunction "DQ9_C2") (pintype "bidirectional"))
      (node (ref "IC1") (pin "L1") (pinfunction "IO_L36N_M3DQ9_3_L1") (pintype "bidirectional"))
    )
    (net (code "41") (name "/DDR2_DQ10") (class "Default")
      (node (ref "DDR2_0") (pin "D7") (pinfunction "DQ10_D7") (pintype "bidirectional"))
      (node (ref "IC1") (pin "M2") (pinfunction "IO_L35P_M3DQ10_3_M2") (pintype "bidirectional"))
    )
    (net (code "42") (name "/DDR2_DQ11") (class "Default")
      (node (ref "DDR2_0") (pin "D3") (pinfunction "DQ11_D3") (pintype "bidirectional"))
      (node (ref "IC1") (pin "M1") (pinfunction "IO_L35N_M3DQ11_3_M1") (pintype "bidirectional"))
    )
    (net (code "43") (name "/DDR2_DQ12") (class "Default")
      (node (ref "DDR2_0") (pin "D1") (pinfunction "DQ12_D1") (pintype "bidirectional"))
      (node (ref "IC1") (pin "P2") (pinfunction "IO_L33P_M3DQ12_3_P2") (pintype "bidirectional"))
    )
    (net (code "44") (name "/DDR2_DQ13") (class "Default")
      (node (ref "DDR2_0") (pin "D9") (pinfunction "DQ13_D9") (pintype "bidirectional"))
      (node (ref "IC1") (pin "P1") (pinfunction "IO_L33N_M3DQ13_3_P1") (pintype "bidirectional"))
    )
    (net (code "45") (name "/DDR2_DQ14") (class "Default")
      (node (ref "DDR2_0") (pin "B1") (pinfunction "DQ14_B1") (pintype "bidirectional"))
      (node (ref "IC1") (pin "R2") (pinfunction "IO_L32P_M3DQ14_3_R2") (pintype "bidirectional"))
    )
    (net (code "46") (name "/DDR2_DQ15") (class "Default")
      (node (ref "DDR2_0") (pin "B9") (pinfunction "DQ15_B9") (pintype "bidirectional"))
      (node (ref "IC1") (pin "R1") (pinfunction "IO_L32N_M3DQ15_3_R1") (pintype "bidirectional"))
    )
    (net (code "47") (name "/DDR2_DQSL") (class "Default")
      (node (ref "DDR2_0") (pin "F7") (pinfunction "DQSL_F7") (pintype "input"))
      (node (ref "IC1") (pin "H2") (pinfunction "IO_L39P_M3LDQS_3_H2") (pintype "bidirectional"))
    )
    (net (code "48") (name "/DDR2_DQSL#") (class "Default")
      (node (ref "DDR2_0") (pin "E8") (pinfunction "DQSL#_E8") (pintype "input"))
      (node (ref "IC1") (pin "H1") (pinfunction "IO_L39N_M3LDQSN_3_H1") (pintype "bidirectional"))
    )
    (net (code "49") (name "/DDR2_DQSU") (class "Default")
      (node (ref "DDR2_0") (pin "B7") (pinfunction "DQSU_B7") (pintype "input"))
      (node (ref "IC1") (pin "N3") (pinfunction "IO_L34P_M3UDQS_3_N3") (pintype "bidirectional"))
    )
    (net (code "50") (name "/DDR2_DQSU#") (class "Default")
      (node (ref "DDR2_0") (pin "A8") (pinfunction "DQSU#_A8") (pintype "input"))
      (node (ref "IC1") (pin "N1") (pinfunction "IO_L34N_M3UDQSN_3_N1") (pintype "bidirectional"))
    )
    (net (code "51") (name "/DDR2_ODT") (class "Default")
      (node (ref "DDR2_0") (pin "K9") (pinfunction "ODT_K9") (pintype "bidirectional"))
      (node (ref "IC1") (pin "L5") (pinfunction "IO_L45N_M3ODT_3_L5") (pintype "bidirectional"))
      (node (ref "R43") (pin "2") (pinfunction "2_2") (pintype "passive"))
    )
    (net (code "52") (name "/DDR2_RAS#") (class "Default")
      (node (ref "DDR2_0") (pin "K7") (pinfunction "RAS#_K7") (pintype "input"))
      (node (ref "IC1") (pin "J6") (pinfunction "IO_L43P_GCLK23_M3RASN_3_J6") (pintype "bidirectional"))
    )
    (net (code "53") (name "/DDR2_WE#") (class "Default")
      (node (ref "DDR2_0") (pin "K3") (pinfunction "WE#_K3") (pintype "input"))
      (node (ref "IC1") (pin "C1") (pinfunction "IO_L50P_M3WE_3_C1") (pintype "bidirectional"))
    )
    (net (code "54") (name "/DDR3_A0") (class "Default")
      (node (ref "DDR3_0") (pin "N3") (pinfunction "A0_N3") (pintype "input"))
      (node (ref "IC1") (pin "H15") (pinfunction "IO_L37P_A7_M1A0_1_H15") (pintype "bidirectional"))
    )
    (net (code "55") (name "/DDR3_A1") (class "Default")
      (node (ref "DDR3_0") (pin "P7") (pinfunction "A1_P7") (pintype "input"))
      (node (ref "IC1") (pin "H16") (pinfunction "IO_L37N_A6_M1A1_1_H16") (pintype "bidirectional"))
    )
    (net (code "56") (name "/DDR3_A2") (class "Default")
      (node (ref "DDR3_0") (pin "P3") (pinfunction "A2_P3") (pintype "input"))
      (node (ref "IC1") (pin "F16") (pinfunction "IO_L35N_A10_M1A2_1_F16") (pintype "bidirectional"))
    )
    (net (code "57") (name "/DDR3_A3") (class "Default")
      (node (ref "DDR3_0") (pin "N2") (pinfunction "A3_N2") (pintype "input"))
      (node (ref "IC1") (pin "H13") (pinfunction "IO_L39P_M1A3_1_H13") (pintype "bidirectional"))
    )
    (net (code "58") (name "/DDR3_A4") (class "Default")
      (node (ref "DDR3_0") (pin "P8") (pinfunction "A4_P8") (pintype "input"))
      (node (ref "IC1") (pin "C16") (pinfunction "IO_L33N_A14_M1A4_1_C16") (pintype "bidirectional"))
    )
    (net (code "59") (name "/DDR3_A5") (class "Default")
      (node (ref "DDR3_0") (pin "P2") (pinfunction "A5_P2") (pintype "input"))
      (node (ref "IC1") (pin "J11") (pinfunction "IO_L40P_GCLK11_M1A5_1_J11") (pintype "bidirectional"))
    )
    (net (code "60") (name "/DDR3_A6") (class "Default")
      (node (ref "DDR3_0") (pin "R8") (pinfunction "A6_R8") (pintype "input"))
      (node (ref "IC1") (pin "J12") (pinfunction "IO_L40N_GCLK10_M1A6_1_J12") (pintype "bidirectional"))
    )
    (net (code "61") (name "/DDR3_A7") (class "Default")
      (node (ref "DDR3_0") (pin "R2") (pinfunction "A7_R2") (pintype "input"))
      (node (ref "IC1") (pin "F15") (pinfunction "IO_L35P_A11_M1A7_1_F15") (pintype "bidirectional"))
    )
    (net (code "62") (name "/DDR3_A8") (class "Default")
      (node (ref "DDR3_0") (pin "T8") (pinfunction "A8_T8") (pintype "input"))
      (node (ref "IC1") (pin "F13") (pinfunction "IO_L32P_A17_M1A8_1_F13") (pintype "bidirectional"))
    )
    (net (code "63") (name "/DDR3_A9") (class "Default")
      (node (ref "DDR3_0") (pin "R3") (pinfunction "A9_R3") (pintype "input"))
      (node (ref "IC1") (pin "F14") (pinfunction "IO_L32N_A16_M1A9_1_F14") (pintype "bidirectional"))
    )
    (net (code "64") (name "/DDR3_A10") (class "Default")
      (node (ref "DDR3_0") (pin "L7") (pinfunction "A10_L7") (pintype "input"))
      (node (ref "IC1") (pin "C15") (pinfunction "IO_L33P_A15_M1A10_1_C15") (pintype "bidirectional"))
    )
    (net (code "65") (name "/DDR3_A11") (class "Default")
      (node (ref "DDR3_0") (pin "R7") (pinfunction "A11_R7") (pintype "input"))
      (node (ref "IC1") (pin "G11") (pinfunction "IO_L30N_A20_M1A11_1_G11") (pintype "bidirectional"))
    )
    (net (code "66") (name "/DDR3_A12") (class "Default")
      (node (ref "DDR3_0") (pin "N7") (pinfunction "A12_N7") (pintype "input"))
      (node (ref "IC1") (pin "D16") (pinfunction "IO_L31N_A18_M1A12_1_D16") (pintype "bidirectional"))
    )
    (net (code "67") (name "/DDR3_A13") (class "Default")
      (node (ref "DDR3_0") (pin "T3") (pinfunction "A13_T3") (pintype "input"))
      (node (ref "IC1") (pin "B15") (pinfunction "IO_L29P_A23_M1A13_1_B15") (pintype "bidirectional"))
    )
    (net (code "68") (name "/DDR3_A14") (class "Default")
      (node (ref "DDR3_0") (pin "T7") (pinfunction "A14_T7") (pintype "input"))
      (node (ref "IC1") (pin "B16") (pinfunction "IO_L29N_A22_M1A14_1_B16") (pintype "bidirectional"))
    )
    (net (code "69") (name "/DDR3_BA0") (class "Default")
      (node (ref "DDR3_0") (pin "M2") (pinfunction "BA0_M2") (pintype "input"))
      (node (ref "IC1") (pin "G14") (pinfunction "IO_L36P_A9_M1BA0_1_G14") (pintype "bidirectional"))
    )
    (net (code "70") (name "/DDR3_BA1") (class "Default")
      (node (ref "DDR3_0") (pin "N8") (pinfunction "BA1_N8") (pintype "input"))
      (node (ref "IC1") (pin "G16") (pinfunction "IO_L36N_A8_M1BA1_1_G16") (pintype "bidirectional"))
    )
    (net (code "71") (name "/DDR3_BA2") (class "Default")
      (node (ref "DDR3_0") (pin "M3") (pinfunction "BA2_M3") (pintype "input"))
      (node (ref "IC1") (pin "E16") (pinfunction "IO_L34N_A12_M1BA2_1_E16") (pintype "bidirectional"))
    )
    (net (code "72") (name "/DDR3_CAS#") (class "Default")
      (node (ref "DDR3_0") (pin "K3") (pinfunction "CAS#_K3") (pintype "input"))
      (node (ref "IC1") (pin "K14") (pinfunction "IO_L41N_GCLK8_M1CASN_1_K14") (pintype "bidirectional"))
    )
    (net (code "73") (name "/DDR3_CK") (class "Default")
      (node (ref "DDR3_0") (pin "J7") (pinfunction "CK_J7") (pintype "input"))
      (node (ref "IC1") (pin "G12") (pinfunction "IO_L38P_A5_M1CLK_1_G12") (pintype "bidirectional"))
      (node (ref "R21") (pin "2") (pinfunction "2_2") (pintype "passive"))
    )
    (net (code "74") (name "/DDR3_CK#") (class "Default")
      (node (ref "DDR3_0") (pin "K7") (pinfunction "CK#_K7") (pintype "input"))
      (node (ref "IC1") (pin "H11") (pinfunction "IO_L38N_A4_M1CLKN_1_H11") (pintype "bidirectional"))
      (node (ref "R21") (pin "1") (pinfunction "1_1") (pintype "passive"))
    )
    (net (code "75") (name "/DDR3_CKE") (class "Default")
      (node (ref "DDR3_0") (pin "K9") (pinfunction "CKE_K9") (pintype "input"))
      (node (ref "IC1") (pin "D14") (pinfunction "IO_L31P_A19_M1CKE_1_D14") (pintype "bidirectional"))
      (node (ref "R40") (pin "2") (pinfunction "2_2") (pintype "passive"))
    )
    (net (code "76") (name "/DDR3_DML") (class "Default")
      (node (ref "DDR3_0") (pin "E7") (pinfunction "DML_E7") (pintype "input"))
      (node (ref "IC1") (pin "K11") (pinfunction "IO_L42N_GCLK6_TRDY1_M1LDM_1_K11") (pintype "bidirectional"))
    )
    (net (code "77") (name "/DDR3_DMU") (class "Default")
      (node (ref "DDR3_0") (pin "D3") (pinfunction "DMU_D3") (pintype "input"))
      (node (ref "IC1") (pin "K12") (pinfunction "IO_L42P_GCLK7_M1UDM_1_K12") (pintype "bidirectional"))
    )
    (net (code "78") (name "/DDR3_DQ0") (class "Default")
      (node (ref "DDR3_0") (pin "E3") (pinfunction "DQ0_E3") (pintype "bidirectional"))
      (node (ref "IC1") (pin "L14") (pinfunction "IO_L47P_FWE_B_M1DQ0_1_L14") (pintype "bidirectional"))
    )
    (net (code "79") (name "/DDR3_DQ1") (class "Default")
      (node (ref "DDR3_0") (pin "F7") (pinfunction "DQ1_F7") (pintype "bidirectional"))
      (node (ref "IC1") (pin "L16") (pinfunction "IO_L47N_LDC_M1DQ1_1_L16") (pintype "bidirectional"))
    )
    (net (code "80") (name "/DDR3_DQ2") (class "Default")
      (node (ref "DDR3_0") (pin "F2") (pinfunction "DQ2_F2") (pintype "bidirectional"))
      (node (ref "IC1") (pin "M15") (pinfunction "IO_L46P_FCS_B_M1DQ2_1_M15") (pintype "bidirectional"))
    )
    (net (code "81") (name "/DDR3_DQ3") (class "Default")
      (node (ref "DDR3_0") (pin "F8") (pinfunction "DQ3_F8") (pintype "bidirectional"))
      (node (ref "IC1") (pin "M16") (pinfunction "IO_L46N_FOE_B_M1DQ3_1_M16") (pintype "bidirectional"))
    )
    (net (code "82") (name "/DDR3_DQ4") (class "Default")
      (node (ref "DDR3_0") (pin "H3") (pinfunction "DQ4_H3") (pintype "bidirectional"))
      (node (ref "IC1") (pin "J14") (pinfunction "IO_L43P_GCLK5_M1DQ4_1_J14") (pintype "bidirectional"))
    )
    (net (code "83") (name "/DDR3_DQ5") (class "Default")
      (node (ref "DDR3_0") (pin "H8") (pinfunction "DQ5_H8") (pintype "bidirectional"))
      (node (ref "IC1") (pin "J16") (pinfunction "IO_L43N_GCLK4_M1DQ5_1_J16") (pintype "bidirectional"))
    )
    (net (code "84") (name "/DDR3_DQ6") (class "Default")
      (node (ref "DDR3_0") (pin "G2") (pinfunction "DQ6_G2") (pintype "bidirectional"))
      (node (ref "IC1") (pin "K15") (pinfunction "IO_L44P_A3_M1DQ6_1_K15") (pintype "bidirectional"))
    )
    (net (code "85") (name "/DDR3_DQ7") (class "Default")
      (node (ref "DDR3_0") (pin "H7") (pinfunction "DQ7_H7") (pintype "bidirectional"))
      (node (ref "IC1") (pin "K16") (pinfunction "IO_L44N_A2_M1DQ7_1_K16") (pintype "bidirectional"))
    )
    (net (code "86") (name "/DDR3_DQ8") (class "Default")
      (node (ref "DDR3_0") (pin "D7") (pinfunction "DQ8_D7") (pintype "bidirectional"))
      (node (ref "IC1") (pin "P15") (pinfunction "IO_L48P_HDC_M1DQ8_1_P15") (pintype "bidirectional"))
    )
    (net (code "87") (name "/DDR3_DQ9") (class "Default")
      (node (ref "DDR3_0") (pin "C3") (pinfunction "DQ9_C3") (pintype "bidirectional"))
      (node (ref "IC1") (pin "P16") (pinfunction "IO_L48N_M1DQ9_1_P16") (pintype "bidirectional"))
    )
    (net (code "88") (name "/DDR3_DQ10") (class "Default")
      (node (ref "DDR3_0") (pin "C8") (pinfunction "DQ10_C8") (pintype "bidirectional"))
      (node (ref "IC1") (pin "R15") (pinfunction "IO_L49P_M1DQ10_1_R15") (pintype "bidirectional"))
    )
    (net (code "89") (name "/DDR3_DQ11") (class "Default")
      (node (ref "DDR3_0") (pin "C2") (pinfunction "DQ11_C2") (pintype "bidirectional"))
      (node (ref "IC1") (pin "R16") (pinfunction "IO_L49N_M1DQ11_1_R16") (pintype "bidirectional"))
    )
    (net (code "90") (name "/DDR3_DQ12") (class "Default")
      (node (ref "DDR3_0") (pin "A7") (pinfunction "DQ12_A7") (pintype "bidirectional"))
      (node (ref "IC1") (pin "T14") (pinfunction "IO_L51P_M1DQ12_1_T14") (pintype "bidirectional"))
    )
    (net (code "91") (name "/DDR3_DQ13") (class "Default")
      (node (ref "DDR3_0") (pin "A2") (pinfunction "DQ13_A2") (pintype "bidirectional"))
      (node (ref "IC1") (pin "T13") (pinfunction "IO_L51N_M1DQ13_1_T13") (pintype "bidirectional"))
    )
    (net (code "92") (name "/DDR3_DQ14") (class "Default")
      (node (ref "DDR3_0") (pin "B8") (pinfunction "DQ14_B8") (pintype "bidirectional"))
      (node (ref "IC1") (pin "R12") (pinfunction "IO_L52P_M1DQ14_1_R12") (pintype "bidirectional"))
    )
    (net (code "93") (name "/DDR3_DQ15") (class "Default")
      (node (ref "DDR3_0") (pin "A3") (pinfunction "DQ15_A3") (pintype "bidirectional"))
      (node (ref "IC1") (pin "T12") (pinfunction "IO_L52N_M1DQ15_1_T12") (pintype "bidirectional"))
    )
    (net (code "94") (name "/DDR3_DQSL") (class "Default")
      (node (ref "DDR3_0") (pin "F3") (pinfunction "DQSL_F3") (pintype "input"))
      (node (ref "IC1") (pin "N14") (pinfunction "IO_L45P_A1_M1LDQS_1_N14") (pintype "bidirectional"))
    )
    (net (code "95") (name "/DDR3_DQSL#") (class "Default")
      (node (ref "DDR3_0") (pin "G3") (pinfunction "DQSL#_G3") (pintype "input"))
      (node (ref "IC1") (pin "N16") (pinfunction "IO_L45N_A0_M1LDQSN_1_N16") (pintype "bidirectional"))
    )
    (net (code "96") (name "/DDR3_DQSU") (class "Default")
      (node (ref "DDR3_0") (pin "C7") (pinfunction "DQSU_C7") (pintype "input"))
      (node (ref "IC1") (pin "R14") (pinfunction "IO_L50P_M1UDQS_1_R14") (pintype "bidirectional"))
    )
    (net (code "97") (name "/DDR3_DQSU#") (class "Default")
      (node (ref "DDR3_0") (pin "B7") (pinfunction "DQSU#_B7") (pintype "input"))
      (node (ref "IC1") (pin "T15") (pinfunction "IO_L50N_M1UDQSN_1_T15") (pintype "bidirectional"))
    )
    (net (code "98") (name "/DDR3_ODT") (class "Default")
      (node (ref "DDR3_0") (pin "K1") (pinfunction "ODT_K1") (pintype "bidirectional"))
      (node (ref "IC1") (pin "H14") (pinfunction "IO_L39N_M1ODT_1_H14") (pintype "bidirectional"))
      (node (ref "R41") (pin "2") (pinfunction "2_2") (pintype "passive"))
    )
    (net (code "99") (name "/DDR3_RAS#") (class "Default")
      (node (ref "DDR3_0") (pin "J3") (pinfunction "RAS#_J3") (pintype "input"))
      (node (ref "IC1") (pin "J13") (pinfunction "IO_L41P_GCLK9_IRDY1_M1RASN_1_J13") (pintype "bidirectional"))
    )
    (net (code "100") (name "/DDR3_RESET#") (class "Default")
      (node (ref "DDR3_0") (pin "T2") (pinfunction "RESET#_T2") (pintype "input"))
      (node (ref "IC1") (pin "F12") (pinfunction "IO_L30P_A21_M1RESET_1_F12") (pintype "bidirectional"))
      (node (ref "R44") (pin "2") (pinfunction "2_2") (pintype "passive"))
    )
    (net (code "101") (name "/DDR3_WE#") (class "Default")
      (node (ref "DDR3_0") (pin "L3") (pinfunction "WE#_L3") (pintype "input"))
      (node (ref "IC1") (pin "E15") (pinfunction "IO_L34P_A13_M1WE_1_E15") (pintype "bidirectional"))
    )
    (net (code "102") (name "/DONE") (class "Default")
      (node (ref "IC1") (pin "P13") (pinfunction "DONE_2_P13") (pintype "bidirectional"))
      (node (ref "R29") (pin "1") (pinfunction "1_1") (pintype "passive"))
      (node (ref "R38") (pin "2") (pinfunction "2_2") (pintype "passive"))
    )
    (net (code "103") (name "/HSWAPEN") (class "Default")
      (node (ref "IC1") (pin "C4") (pinfunction "IO_L1P_HSWAPEN_0_C4") (pintype "bidirectional"))
      (node (ref "SB5") (pin "L1") (pinfunction "P$1_L1") (pintype "passive"))
    )
    (net (code "104") (name "/HSYNC") (class "Default")
      (node (ref "R2") (pin "2") (pinfunction "2_2") (pintype "passive"))
    )
    (net (code "105") (name "/L0") (class "Default")
      (node (ref "R25") (pin "1") (pinfunction "1_1") (pintype "passive"))
    )
    (net (code "106") (name "/L1") (class "Default")
      (node (ref "R19") (pin "1") (pinfunction "1_1") (pintype "passive"))
    )
    (net (code "107") (name "/L2") (class "Default")
      (node (ref "R24") (pin "1") (pinfunction "1_1") (pintype "passive"))
    )
    (net (code "108") (name "/MB_A0") (class "Default")
      (node (ref "SB2") (pin "L1") (pinfunction "P$1_L1") (pintype "passive"))
      (node (ref "U$3") (pin "A15") (pinfunction "A0_A15") (pintype "bidirectional"))
    )
    (net (code "109") (name "/PROGRAM") (class "Default")
      (node (ref "IC1") (pin "T2") (pinfunction "PROGRAM_B_2_T2") (pintype "input"))
      (node (ref "R31") (pin "1") (pinfunction "1_1") (pintype "passive"))
      (node (ref "SB1") (pin "R1") (pinfunction "P$2_R1") (pintype "passive"))
      (node (ref "SB1") (pin "R2") (pinfunction "P$2_R2") (pintype "passive"))
      (node (ref "SB2") (pin "R1") (pinfunction "P$2_R1") (pintype "passive"))
    )
    (net (code "110") (name "/TCK_B") (class "Default")
      (node (ref "IC1") (pin "C14") (pinfunction "TCK_C14") (pintype "input"))
      (node (ref "IC2") (pin "5") (pinfunction "2Y_5") (pintype "bidirectional"))
    )
    (net (code "111") (name "/TCK_I") (class "Default")
      (node (ref "IC2") (pin "3") (pinfunction "2A_3") (pintype "bidirectional"))
      (node (ref "U$3") (pin "B2") (pinfunction "TCK_B2") (pintype "bidirectional"))
    )
    (net (code "112") (name "/TDI_B") (class "Default")
      (node (ref "IC1") (pin "C12") (pinfunction "TDI_C12") (pintype "input"))
      (node (ref "IC2") (pin "7") (pinfunction "1Y_7") (pintype "bidirectional"))
    )
    (net (code "113") (name "/TDI_I") (class "Default")
      (node (ref "IC2") (pin "1") (pinfunction "1A_1") (pintype "bidirectional"))
      (node (ref "U$3") (pin "B1") (pinfunction "TDI_B1") (pintype "output"))
    )
    (net (code "114") (name "/TDO") (class "Default")
      (node (ref "IC1") (pin "E14") (pinfunction "TDO_E14") (pintype "output"))
      (node (ref "U$3") (pin "A1") (pinfunction "TDO_A1") (pintype "input"))
    )
    (net (code "115") (name "/TMS_B") (class "Default")
      (node (ref "IC1") (pin "A15") (pinfunction "TMS_A15") (pintype "input"))
      (node (ref "IC2") (pin "2") (pinfunction "3Y_2") (pintype "bidirectional"))
    )
    (net (code "116") (name "/TMS_I") (class "Default")
      (node (ref "IC2") (pin "6") (pinfunction "3A_6") (pintype "bidirectional"))
      (node (ref "U$3") (pin "A2") (pinfunction "TMS_A2") (pintype "bidirectional"))
    )
    (net (code "117") (name "/VB0") (class "Default")
      (node (ref "R15") (pin "1") (pinfunction "1_1") (pintype "passive"))
    )
    (net (code "118") (name "/VB1") (class "Default")
      (node (ref "R12") (pin "1") (pinfunction "1_1") (pintype "passive"))
    )
    (net (code "119") (name "/VB2") (class "Default")
      (node (ref "R9") (pin "1") (pinfunction "1_1") (pintype "passive"))
    )
    (net (code "120") (name "/VB3") (class "Default")
      (node (ref "R6") (pin "1") (pinfunction "1_1") (pintype "passive"))
    )
    (net (code "121") (name "/VB4") (class "Default")
      (node (ref "R3") (pin "1") (pinfunction "1_1") (pintype "passive"))
    )
    (net (code "122") (name "/VG0") (class "Default")
      (node (ref "R16") (pin "1") (pinfunction "1_1") (pintype "passive"))
    )
    (net (code "123") (name "/VG1") (class "Default")
      (node (ref "R13") (pin "1") (pinfunction "1_1") (pintype "passive"))
    )
    (net (code "124") (name "/VG2") (class "Default")
      (node (ref "R10") (pin "1") (pinfunction "1_1") (pintype "passive"))
    )
    (net (code "125") (name "/VG3") (class "Default")
      (node (ref "R7") (pin "1") (pinfunction "1_1") (pintype "passive"))
    )
    (net (code "126") (name "/VG4") (class "Default")
      (node (ref "R4") (pin "1") (pinfunction "1_1") (pintype "passive"))
    )
    (net (code "127") (name "/VR0") (class "Default")
      (node (ref "R17") (pin "1") (pinfunction "1_1") (pintype "passive"))
    )
    (net (code "128") (name "/VR1") (class "Default")
      (node (ref "R14") (pin "1") (pinfunction "1_1") (pintype "passive"))
    )
    (net (code "129") (name "/VR2") (class "Default")
      (node (ref "R11") (pin "1") (pinfunction "1_1") (pintype "passive"))
    )
    (net (code "130") (name "/VR3") (class "Default")
      (node (ref "R8") (pin "1") (pinfunction "1_1") (pintype "passive"))
    )
    (net (code "131") (name "/VR4") (class "Default")
      (node (ref "R5") (pin "1") (pinfunction "1_1") (pintype "passive"))
    )
    (net (code "132") (name "/VREF_DDR2") (class "Default")
      (node (ref "C27") (pin "1") (pinfunction "1_1") (pintype "passive"))
      (node (ref "C30") (pin "2") (pinfunction "2_2") (pintype "passive"))
      (node (ref "C32") (pin "1") (pinfunction "1_1") (pintype "passive"))
      (node (ref "DDR2_0") (pin "J2") (pinfunction "VREF_J2") (pintype "input"))
      (node (ref "IC1") (pin "A3") (pinfunction "IO_L83N_VREF_3_A3") (pintype "bidirectional"))
      (node (ref "IC1") (pin "M3") (pinfunction "IO_L1N_VREF_3_M3") (pintype "bidirectional"))
      (node (ref "R37") (pin "2") (pinfunction "2_2") (pintype "passive"))
      (node (ref "R39") (pin "1") (pinfunction "1_1") (pintype "passive"))
    )
    (net (code "133") (name "/VREF_DDR3") (class "Default")
      (node (ref "C31") (pin "1") (pinfunction "1_1") (pintype "passive"))
      (node (ref "C7") (pin "1") (pinfunction "1_1") (pintype "passive"))
      (node (ref "C8") (pin "2") (pinfunction "2_2") (pintype "passive"))
      (node (ref "DDR3_0") (pin "H1") (pinfunction "VREFDQ_H1") (pintype "input"))
      (node (ref "DDR3_0") (pin "M8") (pinfunction "VREFCA_M8") (pintype "input"))
      (node (ref "IC1") (pin "E12") (pinfunction "IO_L1N_A24_VREF_1_E12") (pintype "bidirectional"))
      (node (ref "IC1") (pin "L13") (pinfunction "IO_L53N_VREF_1_L13") (pintype "bidirectional"))
      (node (ref "R18") (pin "2") (pinfunction "2_2") (pintype "passive"))
      (node (ref "R36") (pin "1") (pinfunction "1_1") (pintype "passive"))
    )
    (net (code "134") (name "/VSYNC") (class "Default")
      (node (ref "R1") (pin "2") (pinfunction "2_2") (pintype "passive"))
    )
    (net (code "135") (name "/~{GRST}") (class "Default")
      (node (ref "SB1") (pin "L1") (pinfunction "P$1_L1") (pintype "passive"))
      (node (ref "SB1") (pin "L2") (pinfunction "P$1_L2") (pintype "passive"))
      (node (ref "U$3") (pin "B5") (pinfunction "~{GRST}_B5") (pintype "bidirectional"))
    )
    (net (code "136") (name "1.2V") (class "Default")
      (node (ref "C24") (pin "1") (pinfunction "1_1") (pintype "passive"))
      (node (ref "C25") (pin "1") (pinfunction "1_1") (pintype "passive"))
      (node (ref "C26") (pin "1") (pinfunction "1_1") (pintype "passive"))
      (node (ref "C4") (pin "1") (pinfunction "1_1") (pintype "passive"))
      (node (ref "C43") (pin "1") (pinfunction "1_1") (pintype "passive"))
      (node (ref "C49") (pin "1") (pinfunction "1_1") (pintype "passive"))
      (node (ref "C5") (pin "1") (pinfunction "1_1") (pintype "passive"))
      (node (ref "CONN3") (pin "P") (pinfunction "P_P") (pintype "bidirectional"))
      (node (ref "IC1") (pin "G7") (pinfunction "VCCINT_G7") (pintype "input"))
      (node (ref "IC1") (pin "G9") (pinfunction "VCCINT_G9") (pintype "input"))
      (node (ref "IC1") (pin "H10") (pinfunction "VCCINT_H10") (pintype "input"))
      (node (ref "IC1") (pin "H8") (pinfunction "VCCINT_H8") (pintype "input"))
      (node (ref "IC1") (pin "J7") (pinfunction "VCCINT_J7") (pintype "input"))
      (node (ref "IC1") (pin "J9") (pinfunction "VCCINT_J9") (pintype "input"))
      (node (ref "IC1") (pin "K10") (pinfunction "VCCINT_K10") (pintype "input"))
      (node (ref "IC1") (pin "K8") (pinfunction "VCCINT_K8") (pintype "input"))
      (node (ref "U$11") (pin "2") (pinfunction "OUT_2") (pintype "passive"))
      (node (ref "U$11") (pin "4") (pinfunction "OUT_4") (pintype "passive"))
    )
    (net (code "137") (name "1.5V") (class "Default")
      (node (ref "C1") (pin "1") (pinfunction "1_1") (pintype "passive"))
      (node (ref "C2") (pin "1") (pinfunction "1_1") (pintype "passive"))
      (node (ref "C20") (pin "1") (pinfunction "+_1") (pintype "passive"))
      (node (ref "C28") (pin "1") (pinfunction "1_1") (pintype "passive"))
      (node (ref "C29") (pin "1") (pinfunction "1_1") (pintype "passive"))
      (node (ref "C33") (pin "1") (pinfunction "1_1") (pintype "passive"))
      (node (ref "C34") (pin "1") (pinfunction "1_1") (pintype "passive"))
      (node (ref "C35") (pin "1") (pinfunction "1_1") (pintype "passive"))
      (node (ref "C36") (pin "1") (pinfunction "1_1") (pintype "passive"))
      (node (ref "C37") (pin "1") (pinfunction "1_1") (pintype "passive"))
      (node (ref "C44") (pin "1") (pinfunction "1_1") (pintype "passive"))
      (node (ref "C46") (pin "1") (pinfunction "1_1") (pintype "passive"))
      (node (ref "C50") (pin "1") (pinfunction "1_1") (pintype "passive"))
      (node (ref "C8") (pin "1") (pinfunction "1_1") (pintype "passive"))
      (node (ref "CONN5") (pin "P") (pinfunction "P_P") (pintype "bidirectional"))
      (node (ref "DDR3_0") (pin "A1") (pinfunction "VDDQ_A1") (pintype "input"))
      (node (ref "DDR3_0") (pin "A8") (pinfunction "VDDQ_A8") (pintype "input"))
      (node (ref "DDR3_0") (pin "B2") (pinfunction "VDD_B2") (pintype "input"))
      (node (ref "DDR3_0") (pin "C1") (pinfunction "VDDQ_C1") (pintype "input"))
      (node (ref "DDR3_0") (pin "C9") (pinfunction "VDDQ_C9") (pintype "input"))
      (node (ref "DDR3_0") (pin "D2") (pinfunction "VDDQ_D2") (pintype "input"))
      (node (ref "DDR3_0") (pin "D9") (pinfunction "VDD_D9") (pintype "input"))
      (node (ref "DDR3_0") (pin "E9") (pinfunction "VDDQ_E9") (pintype "input"))
      (node (ref "DDR3_0") (pin "F1") (pinfunction "VDDQ_F1") (pintype "input"))
      (node (ref "DDR3_0") (pin "G7") (pinfunction "VDD_G7") (pintype "input"))
      (node (ref "DDR3_0") (pin "H2") (pinfunction "VDDQ_H2") (pintype "input"))
      (node (ref "DDR3_0") (pin "H9") (pinfunction "VDDQ_H9") (pintype "input"))
      (node (ref "DDR3_0") (pin "K2") (pinfunction "VDD_K2") (pintype "input"))
      (node (ref "DDR3_0") (pin "K8") (pinfunction "VDD_K8") (pintype "input"))
      (node (ref "DDR3_0") (pin "N1") (pinfunction "VDD_N1") (pintype "input"))
      (node (ref "DDR3_0") (pin "N9") (pinfunction "VDD_N9") (pintype "input"))
      (node (ref "DDR3_0") (pin "R1") (pinfunction "VDD_R1") (pintype "input"))
      (node (ref "DDR3_0") (pin "R9") (pinfunction "VDD_R9") (pintype "input"))
      (node (ref "IC1") (pin "D15") (pinfunction "VCCO_1_D15") (pintype "input"))
      (node (ref "IC1") (pin "G13") (pinfunction "VCCO_1_G13") (pintype "input"))
      (node (ref "IC1") (pin "J15") (pinfunction "VCCO_1_J15") (pintype "input"))
      (node (ref "IC1") (pin "K13") (pinfunction "VCCO_1_K13") (pintype "input"))
      (node (ref "IC1") (pin "N15") (pinfunction "VCCO_1_N15") (pintype "input"))
      (node (ref "IC1") (pin "R13") (pinfunction "VCCO_1_R13") (pintype "input"))
      (node (ref "R36") (pin "2") (pinfunction "2_2") (pintype "passive"))
      (node (ref "U$13") (pin "2") (pinfunction "OUT_2") (pintype "passive"))
      (node (ref "U$13") (pin "4") (pinfunction "OUT_4") (pintype "passive"))
    )
    (net (code "138") (name "1.8V") (class "Default")
      (node (ref "C12") (pin "1") (pinfunction "1_1") (pintype "passive"))
      (node (ref "C13") (pin "1") (pinfunction "1_1") (pintype "passive"))
      (node (ref "C14") (pin "1") (pinfunction "1_1") (pintype "passive"))
      (node (ref "C21") (pin "1") (pinfunction "+_1") (pintype "passive"))
      (node (ref "C30") (pin "1") (pinfunction "1_1") (pintype "passive"))
      (node (ref "C38") (pin "1") (pinfunction "1_1") (pintype "passive"))
      (node (ref "C39") (pin "1") (pinfunction "1_1") (pintype "passive"))
      (node (ref "C40") (pin "1") (pinfunction "1_1") (pintype "passive"))
      (node (ref "C41") (pin "1") (pinfunction "1_1") (pintype "passive"))
      (node (ref "C42") (pin "1") (pinfunction "1_1") (pintype "passive"))
      (node (ref "C45") (pin "1") (pinfunction "1_1") (pintype "passive"))
      (node (ref "C48") (pin "1") (pinfunction "1_1") (pintype "passive"))
      (node (ref "CONN2") (pin "P") (pinfunction "P_P") (pintype "bidirectional"))
      (node (ref "DDR2_0") (pin "A1") (pinfunction "VDD_A1") (pintype "input"))
      (node (ref "DDR2_0") (pin "A9") (pinfunction "VDDQ_A9") (pintype "input"))
      (node (ref "DDR2_0") (pin "C1") (pinfunction "VDDQ_C1") (pintype "input"))
      (node (ref "DDR2_0") (pin "C3") (pinfunction "VDDQ_C3") (pintype "input"))
      (node (ref "DDR2_0") (pin "C7") (pinfunction "VDDQ_C7") (pintype "input"))
      (node (ref "DDR2_0") (pin "C9") (pinfunction "VDDQ_C9") (pintype "input"))
      (node (ref "DDR2_0") (pin "E1") (pinfunction "VDD_E1") (pintype "input"))
      (node (ref "DDR2_0") (pin "E9") (pinfunction "VDDQ_E9") (pintype "input"))
      (node (ref "DDR2_0") (pin "G1") (pinfunction "VDDQ_G1") (pintype "input"))
      (node (ref "DDR2_0") (pin "G3") (pinfunction "VDDQ_G3") (pintype "input"))
      (node (ref "DDR2_0") (pin "G7") (pinfunction "VDDQ_G7") (pintype "input"))
      (node (ref "DDR2_0") (pin "G9") (pinfunction "VDDQ_G9") (pintype "input"))
      (node (ref "DDR2_0") (pin "J1") (pinfunction "VDDDL_J1") (pintype "input"))
      (node (ref "DDR2_0") (pin "J9") (pinfunction "VDD_J9") (pintype "input"))
      (node (ref "DDR2_0") (pin "M9") (pinfunction "VDD_M9") (pintype "input"))
      (node (ref "DDR2_0") (pin "R1") (pinfunction "VDD_R1") (pintype "input"))
      (node (ref "IC1") (pin "D2") (pinfunction "VCCO_3_D2") (pintype "input"))
      (node (ref "IC1") (pin "G4") (pinfunction "VCCO_3_G4") (pintype "input"))
      (node (ref "IC1") (pin "J2") (pinfunction "VCCO_3_J2") (pintype "input"))
      (node (ref "IC1") (pin "K4") (pinfunction "VCCO_3_K4") (pintype "input"))
      (node (ref "IC1") (pin "N2") (pinfunction "VCCO_3_N2") (pintype "input"))
      (node (ref "R39") (pin "2") (pinfunction "2_2") (pintype "passive"))
      (node (ref "R46") (pin "2") (pinfunction "2_2") (pintype "passive"))
    )
    (net (code "139") (name "3.3V") (class "Default")
      (node (ref "C10") (pin "1") (pinfunction "1_1") (pintype "passive"))
      (node (ref "C11") (pin "1") (pinfunction "1_1") (pintype "passive"))
      (node (ref "C15") (pin "1") (pinfunction "1_1") (pintype "passive"))
      (node (ref "C16") (pin "1") (pinfunction "1_1") (pintype "passive"))
      (node (ref "C17") (pin "1") (pinfunction "1_1") (pintype "passive"))
      (node (ref "C18") (pin "1") (pinfunction "1_1") (pintype "passive"))
      (node (ref "C19") (pin "1") (pinfunction "1_1") (pintype "passive"))
      (node (ref "C3") (pin "1") (pinfunction "1_1") (pintype "passive"))
      (node (ref "C47") (pin "1") (pinfunction "1_1") (pintype "passive"))
      (node (ref "C52") (pin "1") (pinfunction "1_1") (pintype "passive"))
      (node (ref "C6") (pin "1") (pinfunction "1_1") (pintype "passive"))
      (node (ref "C9") (pin "1") (pinfunction "1_1") (pintype "passive"))
      (node (ref "CONN1") (pin "P") (pinfunction "P_P") (pintype "bidirectional"))
      (node (ref "IC1") (pin "B13") (pinfunction "VCCO_0_B13") (pintype "input"))
      (node (ref "IC1") (pin "B4") (pinfunction "VCCO_0_B4") (pintype "input"))
      (node (ref "IC1") (pin "B9") (pinfunction "VCCO_0_B9") (pintype "input"))
      (node (ref "IC1") (pin "D10") (pinfunction "VCCO_0_D10") (pintype "input"))
      (node (ref "IC1") (pin "D7") (pinfunction "VCCO_0_D7") (pintype "input"))
      (node (ref "IC1") (pin "E5") (pinfunction "VCCAUX_E5") (pintype "input"))
      (node (ref "IC1") (pin "F11") (pinfunction "VCCAUX_F11") (pintype "input"))
      (node (ref "IC1") (pin "F8") (pinfunction "VCCAUX_F8") (pintype "input"))
      (node (ref "IC1") (pin "G10") (pinfunction "VCCAUX_G10") (pintype "input"))
      (node (ref "IC1") (pin "H6") (pinfunction "VCCAUX_H6") (pintype "input"))
      (node (ref "IC1") (pin "J10") (pinfunction "VCCAUX_J10") (pintype "input"))
      (node (ref "IC1") (pin "L6") (pinfunction "VCCAUX_L6") (pintype "input"))
      (node (ref "IC1") (pin "L9") (pinfunction "VCCAUX_L9") (pintype "input"))
      (node (ref "IC1") (pin "N10") (pinfunction "VCCO_2_N10") (pintype "input"))
      (node (ref "IC1") (pin "N7") (pinfunction "VCCO_2_N7") (pintype "input"))
      (node (ref "IC1") (pin "R4") (pinfunction "VCCO_2_R4") (pintype "input"))
      (node (ref "IC1") (pin "R8") (pinfunction "VCCO_2_R8") (pintype "input"))
      (node (ref "IC1") (pin "T11") (pinfunction "IO_L1N_M0_CMPMISO_2_T11") (pintype "bidirectional"))
      (node (ref "IC2") (pin "8") (pinfunction "VCC_8") (pintype "bidirectional"))
      (node (ref "L0") (pin "A") (pinfunction "A_A") (pintype "passive"))
      (node (ref "L1") (pin "A") (pinfunction "A_A") (pintype "passive"))
      (node (ref "L2") (pin "A") (pinfunction "A_A") (pintype "passive"))
      (node (ref "R26") (pin "1") (pinfunction "1_1") (pintype "passive"))
      (node (ref "R27") (pin "2") (pinfunction "2_2") (pintype "passive"))
      (node (ref "R28") (pin "2") (pinfunction "2_2") (pintype "passive"))
      (node (ref "R29") (pin "2") (pinfunction "2_2") (pintype "passive"))
      (node (ref "R30") (pin "2") (pinfunction "2_2") (pintype "passive"))
      (node (ref "R31") (pin "2") (pinfunction "2_2") (pintype "passive"))
      (node (ref "R32") (pin "2") (pinfunction "2_2") (pintype "passive"))
      (node (ref "R45") (pin "1") (pinfunction "1_1") (pintype "passive"))
      (node (ref "U$10") (pin "8") (pinfunction "VCC_8") (pintype "bidirectional"))
      (node (ref "U$11") (pin "3") (pinfunction "IN_3") (pintype "input"))
      (node (ref "U$13") (pin "3") (pinfunction "IN_3") (pintype "input"))
      (node (ref "U$6") (pin "1") (pinfunction "EN_1") (pintype "bidirectional"))
      (node (ref "U$6") (pin "4") (pinfunction "VCC_4") (pintype "bidirectional"))
    )
    (net (code "140") (name "GND") (class "Default")
      (node (ref "C1") (pin "2") (pinfunction "2_2") (pintype "passive"))
      (node (ref "C10") (pin "2") (pinfunction "2_2") (pintype "passive"))
      (node (ref "C11") (pin "2") (pinfunction "2_2") (pintype "passive"))
      (node (ref "C12") (pin "2") (pinfunction "2_2") (pintype "passive"))
      (node (ref "C13") (pin "2") (pinfunction "2_2") (pintype "passive"))
      (node (ref "C14") (pin "2") (pinfunction "2_2") (pintype "passive"))
      (node (ref "C15") (pin "2") (pinfunction "2_2") (pintype "passive"))
      (node (ref "C16") (pin "2") (pinfunction "2_2") (pintype "passive"))
      (node (ref "C17") (pin "2") (pinfunction "2_2") (pintype "passive"))
      (node (ref "C18") (pin "2") (pinfunction "2_2") (pintype "passive"))
      (node (ref "C19") (pin "2") (pinfunction "2_2") (pintype "passive"))
      (node (ref "C2") (pin "2") (pinfunction "2_2") (pintype "passive"))
      (node (ref "C20") (pin "2") (pinfunction "-_2") (pintype "passive"))
      (node (ref "C21") (pin "2") (pinfunction "-_2") (pintype "passive"))
      (node (ref "C24") (pin "2") (pinfunction "2_2") (pintype "passive"))
      (node (ref "C25") (pin "2") (pinfunction "2_2") (pintype "passive"))
      (node (ref "C26") (pin "2") (pinfunction "2_2") (pintype "passive"))
      (node (ref "C27") (pin "2") (pinfunction "2_2") (pintype "passive"))
      (node (ref "C28") (pin "2") (pinfunction "2_2") (pintype "passive"))
      (node (ref "C29") (pin "2") (pinfunction "2_2") (pintype "passive"))
      (node (ref "C3") (pin "2") (pinfunction "2_2") (pintype "passive"))
      (node (ref "C31") (pin "2") (pinfunction "2_2") (pintype "passive"))
      (node (ref "C32") (pin "2") (pinfunction "2_2") (pintype "passive"))
      (node (ref "C33") (pin "2") (pinfunction "2_2") (pintype "passive"))
      (node (ref "C34") (pin "2") (pinfunction "2_2") (pintype "passive"))
      (node (ref "C35") (pin "2") (pinfunction "2_2") (pintype "passive"))
      (node (ref "C36") (pin "2") (pinfunction "2_2") (pintype "passive"))
      (node (ref "C37") (pin "2") (pinfunction "2_2") (pintype "passive"))
      (node (ref "C38") (pin "2") (pinfunction "2_2") (pintype "passive"))
      (node (ref "C39") (pin "2") (pinfunction "2_2") (pintype "passive"))
      (node (ref "C4") (pin "2") (pinfunction "2_2") (pintype "passive"))
      (node (ref "C40") (pin "2") (pinfunction "2_2") (pintype "passive"))
      (node (ref "C41") (pin "2") (pinfunction "2_2") (pintype "passive"))
      (node (ref "C42") (pin "2") (pinfunction "2_2") (pintype "passive"))
      (node (ref "C43") (pin "2") (pinfunction "2_2") (pintype "passive"))
      (node (ref "C44") (pin "2") (pinfunction "2_2") (pintype "passive"))
      (node (ref "C45") (pin "2") (pinfunction "2_2") (pintype "passive"))
      (node (ref "C46") (pin "2") (pinfunction "2_2") (pintype "passive"))
      (node (ref "C47") (pin "2") (pinfunction "2_2") (pintype "passive"))
      (node (ref "C48") (pin "2") (pinfunction "2_2") (pintype "passive"))
      (node (ref "C49") (pin "2") (pinfunction "2_2") (pintype "passive"))
      (node (ref "C5") (pin "2") (pinfunction "2_2") (pintype "passive"))
      (node (ref "C50") (pin "2") (pinfunction "2_2") (pintype "passive"))
      (node (ref "C52") (pin "2") (pinfunction "2_2") (pintype "passive"))
      (node (ref "C6") (pin "2") (pinfunction "2_2") (pintype "passive"))
      (node (ref "C7") (pin "2") (pinfunction "2_2") (pintype "passive"))
      (node (ref "C9") (pin "2") (pinfunction "2_2") (pintype "passive"))
      (node (ref "CLIP") (pin "P$1") (pinfunction "P_P$1") (pintype "bidirectional"))
      (node (ref "CLIP") (pin "P$2") (pinfunction "P_P$2") (pintype "bidirectional"))
      (node (ref "CONN4") (pin "P") (pinfunction "P_P") (pintype "bidirectional"))
      (node (ref "DDR2_0") (pin "A3") (pinfunction "VSS_A3") (pintype "input"))
      (node (ref "DDR2_0") (pin "A7") (pinfunction "VSSQ_A7") (pintype "input"))
      (node (ref "DDR2_0") (pin "B2") (pinfunction "VSSQ_B2") (pintype "input"))
      (node (ref "DDR2_0") (pin "B8") (pinfunction "VSSQ_B8") (pintype "input"))
      (node (ref "DDR2_0") (pin "D2") (pinfunction "VSSQ_D2") (pintype "input"))
      (node (ref "DDR2_0") (pin "D8") (pinfunction "VSSQ_D8") (pintype "input"))
      (node (ref "DDR2_0") (pin "E3") (pinfunction "VSS_E3") (pintype "input"))
      (node (ref "DDR2_0") (pin "E7") (pinfunction "VSSQ_E7") (pintype "input"))
      (node (ref "DDR2_0") (pin "F2") (pinfunction "VSSQ_F2") (pintype "input"))
      (node (ref "DDR2_0") (pin "F8") (pinfunction "VSSQ_F8") (pintype "input"))
      (node (ref "DDR2_0") (pin "H2") (pinfunction "VSSQ_H2") (pintype "input"))
      (node (ref "DDR2_0") (pin "H8") (pinfunction "VSSQ_H8") (pintype "input"))
      (node (ref "DDR2_0") (pin "J3") (pinfunction "VSS_J3") (pintype "input"))
      (node (ref "DDR2_0") (pin "J7") (pinfunction "VSSDL_J7") (pintype "input"))
      (node (ref "DDR2_0") (pin "N1") (pinfunction "VSS_N1") (pintype "input"))
      (node (ref "DDR2_0") (pin "P9") (pinfunction "VSS_P9") (pintype "input"))
      (node (ref "DDR3_0") (pin "A9") (pinfunction "VSS_A9") (pintype "input"))
      (node (ref "DDR3_0") (pin "B1") (pinfunction "VSSQ_B1") (pintype "input"))
      (node (ref "DDR3_0") (pin "B3") (pinfunction "VSS_B3") (pintype "input"))
      (node (ref "DDR3_0") (pin "B9") (pinfunction "VSSQ_B9") (pintype "input"))
      (node (ref "DDR3_0") (pin "D1") (pinfunction "VSSQ_D1") (pintype "input"))
      (node (ref "DDR3_0") (pin "D8") (pinfunction "VSSQ_D8") (pintype "input"))
      (node (ref "DDR3_0") (pin "E1") (pinfunction "VSS_E1") (pintype "input"))
      (node (ref "DDR3_0") (pin "E2") (pinfunction "VSSQ_E2") (pintype "input"))
      (node (ref "DDR3_0") (pin "E8") (pinfunction "VSSQ_E8") (pintype "input"))
      (node (ref "DDR3_0") (pin "F9") (pinfunction "VSSQ_F9") (pintype "input"))
      (node (ref "DDR3_0") (pin "G1") (pinfunction "VSSQ_G1") (pintype "input"))
      (node (ref "DDR3_0") (pin "G8") (pinfunction "VSS_G8") (pintype "input"))
      (node (ref "DDR3_0") (pin "G9") (pinfunction "VSSQ_G9") (pintype "input"))
      (node (ref "DDR3_0") (pin "J2") (pinfunction "VSS_J2") (pintype "input"))
      (node (ref "DDR3_0") (pin "J8") (pinfunction "VSS_J8") (pintype "input"))
      (node (ref "DDR3_0") (pin "M1") (pinfunction "VSS_M1") (pintype "input"))
      (node (ref "DDR3_0") (pin "M9") (pinfunction "VSS_M9") (pintype "input"))
      (node (ref "DDR3_0") (pin "P1") (pinfunction "VSS_P1") (pintype "input"))
      (node (ref "DDR3_0") (pin "P9") (pinfunction "VSS_P9") (pintype "input"))
      (node (ref "DDR3_0") (pin "T1") (pinfunction "VSS_T1") (pintype "input"))
      (node (ref "DDR3_0") (pin "T9") (pinfunction "VSS_T9") (pintype "input"))
      (node (ref "IC1") (pin "A1") (pinfunction "GND_A1") (pintype "input"))
      (node (ref "IC1") (pin "A16") (pinfunction "GND_A16") (pintype "input"))
      (node (ref "IC1") (pin "B11") (pinfunction "GND_B11") (pintype "input"))
      (node (ref "IC1") (pin "B7") (pinfunction "GND_B7") (pintype "input"))
      (node (ref "IC1") (pin "D13") (pinfunction "GND_D13") (pintype "input"))
      (node (ref "IC1") (pin "D4") (pinfunction "GND_D4") (pintype "input"))
      (node (ref "IC1") (pin "E9") (pinfunction "GND_E9") (pintype "input"))
      (node (ref "IC1") (pin "G15") (pinfunction "GND_G15") (pintype "input"))
      (node (ref "IC1") (pin "G2") (pinfunction "GND_G2") (pintype "input"))
      (node (ref "IC1") (pin "G8") (pinfunction "GND_G8") (pintype "input"))
      (node (ref "IC1") (pin "H12") (pinfunction "GND_H12") (pintype "input"))
      (node (ref "IC1") (pin "H7") (pinfunction "GND_H7") (pintype "input"))
      (node (ref "IC1") (pin "H9") (pinfunction "GND_H9") (pintype "input"))
      (node (ref "IC1") (pin "J5") (pinfunction "GND_J5") (pintype "input"))
      (node (ref "IC1") (pin "J8") (pinfunction "GND_J8") (pintype "input"))
      (node (ref "IC1") (pin "K7") (pinfunction "GND_K7") (pintype "input"))
      (node (ref "IC1") (pin "K9") (pinfunction "GND_K9") (pintype "input"))
      (node (ref "IC1") (pin "L15") (pinfunction "GND_L15") (pintype "input"))
      (node (ref "IC1") (pin "L2") (pinfunction "GND_L2") (pintype "input"))
      (node (ref "IC1") (pin "M8") (pinfunction "GND_M8") (pintype "input"))
      (node (ref "IC1") (pin "N11") (pinfunction "IO_L13P_M1_2_N11") (pintype "bidirectional"))
      (node (ref "IC1") (pin "N13") (pinfunction "GND_N13") (pintype "input"))
      (node (ref "IC1") (pin "P14") (pinfunction "SUSPEND_P14") (pintype "input"))
      (node (ref "IC1") (pin "P3") (pinfunction "GND_P3") (pintype "input"))
      (node (ref "IC1") (pin "R10") (pinfunction "GND_R10") (pintype "input"))
      (node (ref "IC1") (pin "R6") (pinfunction "GND_R6") (pintype "input"))
      (node (ref "IC1") (pin "T1") (pinfunction "GND_T1") (pintype "input"))
      (node (ref "IC1") (pin "T16") (pinfunction "GND_T16") (pintype "input"))
      (node (ref "IC2") (pin "4") (pinfunction "GND_4") (pintype "bidirectional"))
      (node (ref "LDONE") (pin "C") (pinfunction "C_C") (pintype "passive"))
      (node (ref "LPWR") (pin "C") (pinfunction "C_C") (pintype "passive"))
      (node (ref "R18") (pin "1") (pinfunction "1_1") (pintype "passive"))
      (node (ref "R20") (pin "1") (pinfunction "1_1") (pintype "passive"))
      (node (ref "R22") (pin "2") (pinfunction "2_2") (pintype "passive"))
      (node (ref "R23") (pin "2") (pinfunction "2_2") (pintype "passive"))
      (node (ref "R33") (pin "2") (pinfunction "2_2") (pintype "passive"))
      (node (ref "R34") (pin "1") (pinfunction "1_1") (pintype "passive"))
      (node (ref "R37") (pin "1") (pinfunction "1_1") (pintype "passive"))
      (node (ref "R40") (pin "1") (pinfunction "1_1") (pintype "passive"))
      (node (ref "R41") (pin "1") (pinfunction "1_1") (pintype "passive"))
      (node (ref "R42") (pin "1") (pinfunction "1_1") (pintype "passive"))
      (node (ref "R43") (pin "1") (pinfunction "1_1") (pintype "passive"))
      (node (ref "R44") (pin "1") (pinfunction "1_1") (pintype "passive"))
      (node (ref "SB5") (pin "R1") (pinfunction "P$2_R1") (pintype "passive"))
      (node (ref "U$10") (pin "4") (pinfunction "GND_4") (pintype "bidirectional"))
      (node (ref "U$11") (pin "1") (pinfunction "GND_1") (pintype "input"))
      (node (ref "U$13") (pin "1") (pinfunction "GND_1") (pintype "input"))
      (node (ref "U$3") (pin "A3") (pinfunction "DSEN_A3") (pintype "bidirectional"))
      (node (ref "U$3") (pin "A4") (pinfunction "GND_A4") (pintype "input"))
      (node (ref "U$3") (pin "B3") (pinfunction "MSEN_B3") (pintype "bidirectional"))
      (node (ref "U$3") (pin "B4") (pinfunction "GND_B4") (pintype "input"))
      (node (ref "U$6") (pin "2") (pinfunction "GND_2") (pintype "bidirectional"))
      (node (ref "X2") (pin "10") (pinfunction "10_10") (pintype "passive"))
      (node (ref "X2") (pin "5") (pinfunction "5_5") (pintype "passive"))
      (node (ref "X2") (pin "6") (pinfunction "6_6") (pintype "passive"))
      (node (ref "X2") (pin "7") (pinfunction "7_7") (pintype "passive"))
      (node (ref "X2") (pin "8") (pinfunction "8_8") (pintype "passive"))
    )
    (net (code "141") (name "Net-(DDR2_0-CS#)") (class "Default")
      (node (ref "DDR2_0") (pin "L8") (pinfunction "CS#_L8") (pintype "input"))
      (node (ref "R34") (pin "2") (pinfunction "2_2") (pintype "passive"))
    )
    (net (code "142") (name "Net-(DDR3_0-CS#)") (class "Default")
      (node (ref "DDR3_0") (pin "L2") (pinfunction "CS#_L2") (pintype "input"))
      (node (ref "R20") (pin "2") (pinfunction "2_2") (pintype "passive"))
    )
    (net (code "143") (name "Net-(DDR3_0-ZQ)") (class "Default")
      (node (ref "DDR3_0") (pin "L8") (pinfunction "ZQ_L8") (pintype "bidirectional"))
      (node (ref "R23") (pin "1") (pinfunction "1_1") (pintype "passive"))
    )
    (net (code "144") (name "Net-(IC1-IO_L1P_3)") (class "Default")
      (node (ref "IC1") (pin "M4") (pinfunction "IO_L1P_3_M4") (pintype "bidirectional"))
      (node (ref "R33") (pin "1") (pinfunction "1_1") (pintype "passive"))
    )
    (net (code "145") (name "Net-(IC1-IO_L1P_A25_1)") (class "Default")
      (node (ref "IC1") (pin "E13") (pinfunction "IO_L1P_A25_1_E13") (pintype "bidirectional"))
      (node (ref "R22") (pin "1") (pinfunction "1_1") (pintype "passive"))
    )
    (net (code "146") (name "Net-(IC1-IO_L65P_INIT_B_2)") (class "Default")
      (node (ref "CONN6") (pin "P") (pinfunction "P_P") (pintype "bidirectional"))
      (node (ref "IC1") (pin "R3") (pinfunction "IO_L65P_INIT_B_2_R3") (pintype "bidirectional"))
      (node (ref "R32") (pin "1") (pinfunction "1_1") (pintype "passive"))
    )
    (net (code "147") (name "Net-(L0-PadC)") (class "Default")
      (node (ref "L0") (pin "C") (pinfunction "C_C") (pintype "passive"))
      (node (ref "R19") (pin "2") (pinfunction "2_2") (pintype "passive"))
    )
    (net (code "148") (name "Net-(L1-PadC)") (class "Default")
      (node (ref "L1") (pin "C") (pinfunction "C_C") (pintype "passive"))
      (node (ref "R24") (pin "2") (pinfunction "2_2") (pintype "passive"))
    )
    (net (code "149") (name "Net-(L2-PadC)") (class "Default")
      (node (ref "L2") (pin "C") (pinfunction "C_C") (pintype "passive"))
      (node (ref "R25") (pin "2") (pinfunction "2_2") (pintype "passive"))
    )
    (net (code "150") (name "Net-(LDONE-PadA)") (class "Default")
      (node (ref "LDONE") (pin "A") (pinfunction "A_A") (pintype "passive"))
      (node (ref "R38") (pin "1") (pinfunction "1_1") (pintype "passive"))
    )
    (net (code "151") (name "Net-(LPWR-PadA)") (class "Default")
      (node (ref "LPWR") (pin "A") (pinfunction "A_A") (pintype "passive"))
      (node (ref "R30") (pin "1") (pinfunction "1_1") (pintype "passive"))
    )
    (net (code "152") (name "Net-(R1-Pad1)") (class "Default")
      (node (ref "R1") (pin "1") (pinfunction "1_1") (pintype "passive"))
      (node (ref "X2") (pin "14") (pinfunction "14_14") (pintype "passive"))
    )
    (net (code "153") (name "Net-(R2-Pad1)") (class "Default")
      (node (ref "R2") (pin "1") (pinfunction "1_1") (pintype "passive"))
      (node (ref "X2") (pin "13") (pinfunction "13_13") (pintype "passive"))
    )
    (net (code "154") (name "Net-(R10-Pad2)") (class "Default")
      (node (ref "R10") (pin "2") (pinfunction "2_2") (pintype "passive"))
      (node (ref "R13") (pin "2") (pinfunction "2_2") (pintype "passive"))
      (node (ref "R16") (pin "2") (pinfunction "2_2") (pintype "passive"))
      (node (ref "R4") (pin "2") (pinfunction "2_2") (pintype "passive"))
      (node (ref "R7") (pin "2") (pinfunction "2_2") (pintype "passive"))
      (node (ref "X2") (pin "2") (pinfunction "2_2") (pintype "passive"))
    )
    (net (code "155") (name "Net-(R11-Pad2)") (class "Default")
      (node (ref "R11") (pin "2") (pinfunction "2_2") (pintype "passive"))
      (node (ref "R14") (pin "2") (pinfunction "2_2") (pintype "passive"))
      (node (ref "R17") (pin "2") (pinfunction "2_2") (pintype "passive"))
      (node (ref "R5") (pin "2") (pinfunction "2_2") (pintype "passive"))
      (node (ref "R8") (pin "2") (pinfunction "2_2") (pintype "passive"))
      (node (ref "X2") (pin "1") (pinfunction "1_1") (pintype "passive"))
    )
    (net (code "156") (name "Net-(R12-Pad2)") (class "Default")
      (node (ref "R12") (pin "2") (pinfunction "2_2") (pintype "passive"))
      (node (ref "R15") (pin "2") (pinfunction "2_2") (pintype "passive"))
      (node (ref "R3") (pin "2") (pinfunction "2_2") (pintype "passive"))
      (node (ref "R6") (pin "2") (pinfunction "2_2") (pintype "passive"))
      (node (ref "R9") (pin "2") (pinfunction "2_2") (pintype "passive"))
      (node (ref "X2") (pin "3") (pinfunction "3_3") (pintype "passive"))
    )
    (net (code "157") (name "Net-(U$3-1.8V)") (class "Default")
      (node (ref "R46") (pin "1") (pinfunction "1_1") (pintype "passive"))
      (node (ref "U$3") (pin "B7") (pinfunction "1.8V_B7") (pintype "bidirectional"))
    )
    (net (code "158") (name "Net-(U$3-3.3V)") (class "Default")
      (node (ref "R45") (pin "2") (pinfunction "2_2") (pintype "passive"))
      (node (ref "U$3") (pin "A7") (pinfunction "3.3V_A7") (pintype "bidirectional"))
    )
    (net (code "159") (name "unconnected-(IC1-CMPCS_B_2-PadL11)") (class "Default")
      (node (ref "IC1") (pin "L11") (pinfunction "CMPCS_B_2_L11") (pintype "bidirectional"))
    )
    (net (code "160") (name "unconnected-(IC1-IO_L1N_VREF_0-PadA4)") (class "Default")
      (node (ref "IC1") (pin "A4") (pinfunction "IO_L1N_VREF_0_A4") (pintype "bidirectional"))
    )
    (net (code "161") (name "unconnected-(IC1-IO_L2N_0-PadA5)") (class "Default")
      (node (ref "IC1") (pin "A5") (pinfunction "IO_L2N_0_A5") (pintype "bidirectional"))
    )
    (net (code "162") (name "unconnected-(IC1-IO_L2N_3-PadN4)") (class "Default")
      (node (ref "IC1") (pin "N4") (pinfunction "IO_L2N_3_N4") (pintype "bidirectional"))
    )
    (net (code "163") (name "unconnected-(IC1-IO_L2N_CMPMOSI_2-PadM11)") (class "Default")
      (node (ref "IC1") (pin "M11") (pinfunction "IO_L2N_CMPMOSI_2_M11") (pintype "bidirectional"))
    )
    (net (code "164") (name "unconnected-(IC1-IO_L2P_0-PadB5)") (class "Default")
      (node (ref "IC1") (pin "B5") (pinfunction "IO_L2P_0_B5") (pintype "bidirectional"))
    )
    (net (code "165") (name "unconnected-(IC1-IO_L2P_3-PadM5)") (class "Default")
      (node (ref "IC1") (pin "M5") (pinfunction "IO_L2P_3_M5") (pintype "bidirectional"))
    )
    (net (code "166") (name "unconnected-(IC1-IO_L2P_CMPCLK_2-PadM12)") (class "Default")
      (node (ref "IC1") (pin "M12") (pinfunction "IO_L2P_CMPCLK_2_M12") (pintype "bidirectional"))
    )
    (net (code "167") (name "unconnected-(IC1-IO_L3N_0-PadC5)") (class "Default")
      (node (ref "IC1") (pin "C5") (pinfunction "IO_L3N_0_C5") (pintype "bidirectional"))
    )
    (net (code "168") (name "unconnected-(IC1-IO_L3P_0-PadD5)") (class "Default")
      (node (ref "IC1") (pin "D5") (pinfunction "IO_L3P_0_D5") (pintype "bidirectional"))
    )
    (net (code "169") (name "unconnected-(IC1-IO_L4N_0-PadA6)") (class "Default")
      (node (ref "IC1") (pin "A6") (pinfunction "IO_L4N_0_A6") (pintype "bidirectional"))
    )
    (net (code "170") (name "unconnected-(IC1-IO_L4P_0-PadB6)") (class "Default")
      (node (ref "IC1") (pin "B6") (pinfunction "IO_L4P_0_B6") (pintype "bidirectional"))
    )
    (net (code "171") (name "unconnected-(IC1-IO_L5N_0-PadE6)") (class "Default")
      (node (ref "IC1") (pin "E6") (pinfunction "IO_L5N_0_E6") (pintype "bidirectional"))
    )
    (net (code "172") (name "unconnected-(IC1-IO_L5P_0-PadF7)") (class "Default")
      (node (ref "IC1") (pin "F7") (pinfunction "IO_L5P_0_F7") (pintype "bidirectional"))
    )
    (net (code "173") (name "unconnected-(IC1-IO_L6N_0-PadA7)") (class "Default")
      (node (ref "IC1") (pin "A7") (pinfunction "IO_L6N_0_A7") (pintype "bidirectional"))
    )
    (net (code "174") (name "unconnected-(IC1-IO_L6P_0-PadC7)") (class "Default")
      (node (ref "IC1") (pin "C7") (pinfunction "IO_L6P_0_C7") (pintype "bidirectional"))
    )
    (net (code "175") (name "unconnected-(IC1-IO_L7N_0-PadC6)") (class "Default")
      (node (ref "IC1") (pin "C6") (pinfunction "IO_L7N_0_C6") (pintype "bidirectional"))
    )
    (net (code "176") (name "unconnected-(IC1-IO_L7P_0-PadD6)") (class "Default")
      (node (ref "IC1") (pin "D6") (pinfunction "IO_L7P_0_D6") (pintype "bidirectional"))
    )
    (net (code "177") (name "unconnected-(IC1-IO_L13N_D10_2-PadP11)") (class "Default")
      (node (ref "IC1") (pin "P11") (pinfunction "IO_L13N_D10_2_P11") (pintype "bidirectional"))
    )
    (net (code "178") (name "unconnected-(IC1-IO_L14N_D12_2-PadP9)") (class "Default")
      (node (ref "IC1") (pin "P9") (pinfunction "IO_L14N_D12_2_P9") (pintype "bidirectional"))
    )
    (net (code "179") (name "unconnected-(IC1-IO_L14P_D11_2-PadN9)") (class "Default")
      (node (ref "IC1") (pin "N9") (pinfunction "IO_L14P_D11_2_N9") (pintype "bidirectional"))
    )
    (net (code "180") (name "unconnected-(IC1-IO_L16N_VREF_2-PadM10)") (class "Default")
      (node (ref "IC1") (pin "M10") (pinfunction "IO_L16N_VREF_2_M10") (pintype "bidirectional"))
    )
    (net (code "181") (name "unconnected-(IC1-IO_L16P_2-PadL10)") (class "Default")
      (node (ref "IC1") (pin "L10") (pinfunction "IO_L16P_2_L10") (pintype "bidirectional"))
    )
    (net (code "182") (name "unconnected-(IC1-IO_L23N_2-PadT9)") (class "Default")
      (node (ref "IC1") (pin "T9") (pinfunction "IO_L23N_2_T9") (pintype "bidirectional"))
    )
    (net (code "183") (name "unconnected-(IC1-IO_L23P_2-PadR9)") (class "Default")
      (node (ref "IC1") (pin "R9") (pinfunction "IO_L23P_2_R9") (pintype "bidirectional"))
    )
    (net (code "184") (name "unconnected-(IC1-IO_L29N_GCLK2_2-PadN8)") (class "Default")
      (node (ref "IC1") (pin "N8") (pinfunction "IO_L29N_GCLK2_2_N8") (pintype "bidirectional"))
    )
    (net (code "185") (name "unconnected-(IC1-IO_L29P_GCLK3_2-PadM9)") (class "Default")
      (node (ref "IC1") (pin "M9") (pinfunction "IO_L29P_GCLK3_2_M9") (pintype "bidirectional"))
    )
    (net (code "186") (name "unconnected-(IC1-IO_L30N_GCLK0_USERCCLK_2-PadT8)") (class "Default")
      (node (ref "IC1") (pin "T8") (pinfunction "IO_L30N_GCLK0_USERCCLK_2_T8") (pintype "bidirectional"))
    )
    (net (code "187") (name "unconnected-(IC1-IO_L30P_GCLK1_D13_2-PadP8)") (class "Default")
      (node (ref "IC1") (pin "P8") (pinfunction "IO_L30P_GCLK1_D13_2_P8") (pintype "bidirectional"))
    )
    (net (code "188") (name "unconnected-(IC1-IO_L31N_GCLK30_D15_2-PadM7)") (class "Default")
      (node (ref "IC1") (pin "M7") (pinfunction "IO_L31N_GCLK30_D15_2_M7") (pintype "bidirectional"))
    )
    (net (code "189") (name "unconnected-(IC1-IO_L31P_GCLK31_D14_2-PadP7)") (class "Default")
      (node (ref "IC1") (pin "P7") (pinfunction "IO_L31P_GCLK31_D14_2_P7") (pintype "bidirectional"))
    )
    (net (code "190") (name "unconnected-(IC1-IO_L32N_GCLK28_2-PadT7)") (class "Default")
      (node (ref "IC1") (pin "T7") (pinfunction "IO_L32N_GCLK28_2_T7") (pintype "bidirectional"))
    )
    (net (code "191") (name "unconnected-(IC1-IO_L32P_GCLK29_2-PadR7)") (class "Default")
      (node (ref "IC1") (pin "R7") (pinfunction "IO_L32P_GCLK29_2_R7") (pintype "bidirectional"))
    )
    (net (code "192") (name "unconnected-(IC1-IO_L33N_0-PadA8)") (class "Default")
      (node (ref "IC1") (pin "A8") (pinfunction "IO_L33N_0_A8") (pintype "bidirectional"))
    )
    (net (code "193") (name "unconnected-(IC1-IO_L33P_0-PadB8)") (class "Default")
      (node (ref "IC1") (pin "B8") (pinfunction "IO_L33P_0_B8") (pintype "bidirectional"))
    )
    (net (code "194") (name "unconnected-(IC1-IO_L34N_GCLK18_0-PadA9)") (class "Default")
      (node (ref "IC1") (pin "A9") (pinfunction "IO_L34N_GCLK18_0_A9") (pintype "bidirectional"))
    )
    (net (code "195") (name "unconnected-(IC1-IO_L34P_GCLK19_0-PadC9)") (class "Default")
      (node (ref "IC1") (pin "C9") (pinfunction "IO_L34P_GCLK19_0_C9") (pintype "bidirectional"))
    )
    (net (code "196") (name "unconnected-(IC1-IO_L35N_GCLK16_0-PadA10)") (class "Default")
      (node (ref "IC1") (pin "A10") (pinfunction "IO_L35N_GCLK16_0_A10") (pintype "bidirectional"))
    )
    (net (code "197") (name "unconnected-(IC1-IO_L35P_GCLK17_0-PadB10)") (class "Default")
      (node (ref "IC1") (pin "B10") (pinfunction "IO_L35P_GCLK17_0_B10") (pintype "bidirectional"))
    )
    (net (code "198") (name "unconnected-(IC1-IO_L36N_GCLK14_0-PadE8)") (class "Default")
      (node (ref "IC1") (pin "E8") (pinfunction "IO_L36N_GCLK14_0_E8") (pintype "bidirectional"))
    )
    (net (code "199") (name "unconnected-(IC1-IO_L36P_GCLK15_0-PadE7)") (class "Default")
      (node (ref "IC1") (pin "E7") (pinfunction "IO_L36P_GCLK15_0_E7") (pintype "bidirectional"))
    )
    (net (code "200") (name "unconnected-(IC1-IO_L37N_GCLK12_0-PadC10)") (class "Default")
      (node (ref "IC1") (pin "C10") (pinfunction "IO_L37N_GCLK12_0_C10") (pintype "bidirectional"))
    )
    (net (code "201") (name "unconnected-(IC1-IO_L37P_GCLK13_0-PadE10)") (class "Default")
      (node (ref "IC1") (pin "E10") (pinfunction "IO_L37P_GCLK13_0_E10") (pintype "bidirectional"))
    )
    (net (code "202") (name "unconnected-(IC1-IO_L38N_VREF_0-PadC8)") (class "Default")
      (node (ref "IC1") (pin "C8") (pinfunction "IO_L38N_VREF_0_C8") (pintype "bidirectional"))
    )
    (net (code "203") (name "unconnected-(IC1-IO_L38P_0-PadD8)") (class "Default")
      (node (ref "IC1") (pin "D8") (pinfunction "IO_L38P_0_D8") (pintype "bidirectional"))
    )
    (net (code "204") (name "unconnected-(IC1-IO_L39N_0-PadA11)") (class "Default")
      (node (ref "IC1") (pin "A11") (pinfunction "IO_L39N_0_A11") (pintype "bidirectional"))
    )
    (net (code "205") (name "unconnected-(IC1-IO_L39P_0-PadC11)") (class "Default")
      (node (ref "IC1") (pin "C11") (pinfunction "IO_L39P_0_C11") (pintype "bidirectional"))
    )
    (net (code "206") (name "unconnected-(IC1-IO_L40N_0-PadD9)") (class "Default")
      (node (ref "IC1") (pin "D9") (pinfunction "IO_L40N_0_D9") (pintype "bidirectional"))
    )
    (net (code "207") (name "unconnected-(IC1-IO_L40P_0-PadF9)") (class "Default")
      (node (ref "IC1") (pin "F9") (pinfunction "IO_L40P_0_F9") (pintype "bidirectional"))
    )
    (net (code "208") (name "unconnected-(IC1-IO_L47N_2-PadT6)") (class "Default")
      (node (ref "IC1") (pin "T6") (pinfunction "IO_L47N_2_T6") (pintype "bidirectional"))
    )
    (net (code "209") (name "unconnected-(IC1-IO_L47P_2-PadP6)") (class "Default")
      (node (ref "IC1") (pin "P6") (pinfunction "IO_L47P_2_P6") (pintype "bidirectional"))
    )
    (net (code "210") (name "unconnected-(IC1-IO_L48N_RDWR_B_VREF_2-PadT5)") (class "Default")
      (node (ref "IC1") (pin "T5") (pinfunction "IO_L48N_RDWR_B_VREF_2_T5") (pintype "bidirectional"))
    )
    (net (code "211") (name "unconnected-(IC1-IO_L48P_D7_2-PadR5)") (class "Default")
      (node (ref "IC1") (pin "R5") (pinfunction "IO_L48P_D7_2_R5") (pintype "bidirectional"))
    )
    (net (code "212") (name "unconnected-(IC1-IO_L49N_D4_2-PadP5)") (class "Default")
      (node (ref "IC1") (pin "P5") (pinfunction "IO_L49N_D4_2_P5") (pintype "bidirectional"))
    )
    (net (code "213") (name "unconnected-(IC1-IO_L49P_D3_2-PadN5)") (class "Default")
      (node (ref "IC1") (pin "N5") (pinfunction "IO_L49P_D3_2_N5") (pintype "bidirectional"))
    )
    (net (code "214") (name "unconnected-(IC1-IO_L53P_1-PadL12)") (class "Default")
      (node (ref "IC1") (pin "L12") (pinfunction "IO_L53P_1_L12") (pintype "bidirectional"))
    )
    (net (code "215") (name "unconnected-(IC1-IO_L54P_M3RESET_3-PadE4)") (class "Default")
      (node (ref "IC1") (pin "E4") (pinfunction "IO_L54P_M3RESET_3_E4") (pintype "bidirectional"))
    )
    (net (code "216") (name "unconnected-(IC1-IO_L55N_M3A14_3-PadF5)") (class "Default")
      (node (ref "IC1") (pin "F5") (pinfunction "IO_L55N_M3A14_3_F5") (pintype "bidirectional"))
    )
    (net (code "217") (name "unconnected-(IC1-IO_L62N_D6_2-PadL7)") (class "Default")
      (node (ref "IC1") (pin "L7") (pinfunction "IO_L62N_D6_2_L7") (pintype "bidirectional"))
    )
    (net (code "218") (name "unconnected-(IC1-IO_L62N_VREF_0-PadA12)") (class "Default")
      (node (ref "IC1") (pin "A12") (pinfunction "IO_L62N_VREF_0_A12") (pintype "bidirectional"))
    )
    (net (code "219") (name "unconnected-(IC1-IO_L62P_0-PadB12)") (class "Default")
      (node (ref "IC1") (pin "B12") (pinfunction "IO_L62P_0_B12") (pintype "bidirectional"))
    )
    (net (code "220") (name "unconnected-(IC1-IO_L62P_D5_2-PadL8)") (class "Default")
      (node (ref "IC1") (pin "L8") (pinfunction "IO_L62P_D5_2_L8") (pintype "bidirectional"))
    )
    (net (code "221") (name "unconnected-(IC1-IO_L63N_2-PadT4)") (class "Default")
      (node (ref "IC1") (pin "T4") (pinfunction "IO_L63N_2_T4") (pintype "bidirectional"))
    )
    (net (code "222") (name "unconnected-(IC1-IO_L63N_SCP6_0-PadA13)") (class "Default")
      (node (ref "IC1") (pin "A13") (pinfunction "IO_L63N_SCP6_0_A13") (pintype "bidirectional"))
    )
    (net (code "223") (name "unconnected-(IC1-IO_L63P_2-PadP4)") (class "Default")
      (node (ref "IC1") (pin "P4") (pinfunction "IO_L63P_2_P4") (pintype "bidirectional"))
    )
    (net (code "224") (name "unconnected-(IC1-IO_L63P_SCP7_0-PadC13)") (class "Default")
      (node (ref "IC1") (pin "C13") (pinfunction "IO_L63P_SCP7_0_C13") (pintype "bidirectional"))
    )
    (net (code "225") (name "unconnected-(IC1-IO_L64N_D9_2-PadN6)") (class "Default")
      (node (ref "IC1") (pin "N6") (pinfunction "IO_L64N_D9_2_N6") (pintype "bidirectional"))
    )
    (net (code "226") (name "unconnected-(IC1-IO_L64N_SCP4_0-PadE11)") (class "Default")
      (node (ref "IC1") (pin "E11") (pinfunction "IO_L64N_SCP4_0_E11") (pintype "bidirectional"))
    )
    (net (code "227") (name "unconnected-(IC1-IO_L64P_D8_2-PadM6)") (class "Default")
      (node (ref "IC1") (pin "M6") (pinfunction "IO_L64P_D8_2_M6") (pintype "bidirectional"))
    )
    (net (code "228") (name "unconnected-(IC1-IO_L64P_SCP5_0-PadF10)") (class "Default")
      (node (ref "IC1") (pin "F10") (pinfunction "IO_L64P_SCP5_0_F10") (pintype "bidirectional"))
    )
    (net (code "229") (name "unconnected-(IC1-IO_L65N_SCP2_0-PadA14)") (class "Default")
      (node (ref "IC1") (pin "A14") (pinfunction "IO_L65N_SCP2_0_A14") (pintype "bidirectional"))
    )
    (net (code "230") (name "unconnected-(IC1-IO_L65P_SCP3_0-PadB14)") (class "Default")
      (node (ref "IC1") (pin "B14") (pinfunction "IO_L65P_SCP3_0_B14") (pintype "bidirectional"))
    )
    (net (code "231") (name "unconnected-(IC1-IO_L66N_SCP0_0-PadD12)") (class "Default")
      (node (ref "IC1") (pin "D12") (pinfunction "IO_L66N_SCP0_0_D12") (pintype "bidirectional"))
    )
    (net (code "232") (name "unconnected-(IC1-IO_L66P_SCP1_0-PadD11)") (class "Default")
      (node (ref "IC1") (pin "D11") (pinfunction "IO_L66P_SCP1_0_D11") (pintype "bidirectional"))
    )
    (net (code "233") (name "unconnected-(IC1-IO_L74N_DOUT_BUSY_1-PadM14)") (class "Default")
      (node (ref "IC1") (pin "M14") (pinfunction "IO_L74N_DOUT_BUSY_1_M14") (pintype "bidirectional"))
    )
    (net (code "234") (name "unconnected-(IC1-IO_L74P_AWAKE_1-PadM13)") (class "Default")
      (node (ref "IC1") (pin "M13") (pinfunction "IO_L74P_AWAKE_1_M13") (pintype "bidirectional"))
    )
    (net (code "235") (name "unconnected-(IC1-IO_L83P_3-PadB3)") (class "Default")
      (node (ref "IC1") (pin "B3") (pinfunction "IO_L83P_3_B3") (pintype "bidirectional"))
    )
    (net (code "236") (name "unconnected-(IC3A-A0-Pad23)") (class "Default")
      (node (ref "IC3") (pin "23") (pinfunction "A0_23") (pintype "input"))
    )
    (net (code "237") (name "unconnected-(IC3A-A1-Pad24)") (class "Default")
      (node (ref "IC3") (pin "24") (pinfunction "A1_24") (pintype "input"))
    )
    (net (code "238") (name "unconnected-(IC3A-A2-Pad25)") (class "Default")
      (node (ref "IC3") (pin "25") (pinfunction "A2_25") (pintype "input"))
    )
    (net (code "239") (name "unconnected-(IC3A-A3-Pad26)") (class "Default")
      (node (ref "IC3") (pin "26") (pinfunction "A3_26") (pintype "input"))
    )
    (net (code "240") (name "unconnected-(IC3A-A4-Pad29)") (class "Default")
      (node (ref "IC3") (pin "29") (pinfunction "A4_29") (pintype "input"))
    )
    (net (code "241") (name "unconnected-(IC3A-A5-Pad30)") (class "Default")
      (node (ref "IC3") (pin "30") (pinfunction "A5_30") (pintype "input"))
    )
    (net (code "242") (name "unconnected-(IC3A-A6-Pad31)") (class "Default")
      (node (ref "IC3") (pin "31") (pinfunction "A6_31") (pintype "input"))
    )
    (net (code "243") (name "unconnected-(IC3A-A7-Pad32)") (class "Default")
      (node (ref "IC3") (pin "32") (pinfunction "A7_32") (pintype "input"))
    )
    (net (code "244") (name "unconnected-(IC3A-A8-Pad33)") (class "Default")
      (node (ref "IC3") (pin "33") (pinfunction "A8_33") (pintype "input"))
    )
    (net (code "245") (name "unconnected-(IC3A-A9-Pad34)") (class "Default")
      (node (ref "IC3") (pin "34") (pinfunction "A9_34") (pintype "input"))
    )
    (net (code "246") (name "unconnected-(IC3A-A10-Pad22)") (class "Default")
      (node (ref "IC3") (pin "22") (pinfunction "A10_22") (pintype "input"))
    )
    (net (code "247") (name "unconnected-(IC3A-A11-Pad35)") (class "Default")
      (node (ref "IC3") (pin "35") (pinfunction "A11_35") (pintype "input"))
    )
    (net (code "248") (name "unconnected-(IC3A-A12-Pad36)") (class "Default")
      (node (ref "IC3") (pin "36") (pinfunction "A12_36") (pintype "input"))
    )
    (net (code "249") (name "unconnected-(IC3A-BA0-Pad20)") (class "Default")
      (node (ref "IC3") (pin "20") (pinfunction "BA0_20") (pintype "input"))
    )
    (net (code "250") (name "unconnected-(IC3A-BA1-Pad21)") (class "Default")
      (node (ref "IC3") (pin "21") (pinfunction "BA1_21") (pintype "input"))
    )
    (net (code "251") (name "unconnected-(IC3A-CKE-Pad37)") (class "Default")
      (node (ref "IC3") (pin "37") (pinfunction "CKE_37") (pintype "input"))
    )
    (net (code "252") (name "unconnected-(IC3A-CLK-Pad38)") (class "Default")
      (node (ref "IC3") (pin "38") (pinfunction "CLK_38") (pintype "input"))
    )
    (net (code "253") (name "unconnected-(IC3A-DQ0-Pad2)") (class "Default")
      (node (ref "IC3") (pin "2") (pinfunction "DQ0_2") (pintype "tri_state"))
    )
    (net (code "254") (name "unconnected-(IC3A-DQ1-Pad4)") (class "Default")
      (node (ref "IC3") (pin "4") (pinfunction "DQ1_4") (pintype "tri_state"))
    )
    (net (code "255") (name "unconnected-(IC3A-DQ2-Pad5)") (class "Default")
      (node (ref "IC3") (pin "5") (pinfunction "DQ2_5") (pintype "tri_state"))
    )
    (net (code "256") (name "unconnected-(IC3A-DQ3-Pad7)") (class "Default")
      (node (ref "IC3") (pin "7") (pinfunction "DQ3_7") (pintype "tri_state"))
    )
    (net (code "257") (name "unconnected-(IC3A-DQ4-Pad8)") (class "Default")
      (node (ref "IC3") (pin "8") (pinfunction "DQ4_8") (pintype "tri_state"))
    )
    (net (code "258") (name "unconnected-(IC3A-DQ5-Pad10)") (class "Default")
      (node (ref "IC3") (pin "10") (pinfunction "DQ5_10") (pintype "tri_state"))
    )
    (net (code "259") (name "unconnected-(IC3A-DQ6-Pad11)") (class "Default")
      (node (ref "IC3") (pin "11") (pinfunction "DQ6_11") (pintype "tri_state"))
    )
    (net (code "260") (name "unconnected-(IC3A-DQ7-Pad13)") (class "Default")
      (node (ref "IC3") (pin "13") (pinfunction "DQ7_13") (pintype "tri_state"))
    )
    (net (code "261") (name "unconnected-(IC3A-DQ8-Pad42)") (class "Default")
      (node (ref "IC3") (pin "42") (pinfunction "DQ8_42") (pintype "tri_state"))
    )
    (net (code "262") (name "unconnected-(IC3A-DQ9-Pad44)") (class "Default")
      (node (ref "IC3") (pin "44") (pinfunction "DQ9_44") (pintype "tri_state"))
    )
    (net (code "263") (name "unconnected-(IC3A-DQ10-Pad45)") (class "Default")
      (node (ref "IC3") (pin "45") (pinfunction "DQ10_45") (pintype "tri_state"))
    )
    (net (code "264") (name "unconnected-(IC3A-DQ11-Pad47)") (class "Default")
      (node (ref "IC3") (pin "47") (pinfunction "DQ11_47") (pintype "tri_state"))
    )
    (net (code "265") (name "unconnected-(IC3A-DQ12-Pad48)") (class "Default")
      (node (ref "IC3") (pin "48") (pinfunction "DQ12_48") (pintype "tri_state"))
    )
    (net (code "266") (name "unconnected-(IC3A-DQ13-Pad50)") (class "Default")
      (node (ref "IC3") (pin "50") (pinfunction "DQ13_50") (pintype "tri_state"))
    )
    (net (code "267") (name "unconnected-(IC3A-DQ14-Pad51)") (class "Default")
      (node (ref "IC3") (pin "51") (pinfunction "DQ14_51") (pintype "tri_state"))
    )
    (net (code "268") (name "unconnected-(IC3A-DQ15-Pad53)") (class "Default")
      (node (ref "IC3") (pin "53") (pinfunction "DQ15_53") (pintype "tri_state"))
    )
    (net (code "269") (name "unconnected-(IC3A-DQMH-Pad39)") (class "Default")
      (node (ref "IC3") (pin "39") (pinfunction "DQMH_39") (pintype "input"))
    )
    (net (code "270") (name "unconnected-(IC3A-DQML-Pad15)") (class "Default")
      (node (ref "IC3") (pin "15") (pinfunction "DQML_15") (pintype "input"))
    )
    (net (code "271") (name "unconnected-(IC3A-NC-Pad40)") (class "Default")
      (node (ref "IC3") (pin "40") (pinfunction "NC_40") (pintype "no_connect"))
    )
    (net (code "272") (name "unconnected-(IC3A-\\CS-Pad19)") (class "Default")
      (node (ref "IC3") (pin "19") (pinfunction "\\CS_19") (pintype "input"))
    )
    (net (code "273") (name "unconnected-(IC3A-~{CAS}-Pad17)") (class "Default")
      (node (ref "IC3") (pin "17") (pinfunction "~{CAS}_17") (pintype "input"))
    )
    (net (code "274") (name "unconnected-(IC3A-~{RAS}-Pad18)") (class "Default")
      (node (ref "IC3") (pin "18") (pinfunction "~{RAS}_18") (pintype "input"))
    )
    (net (code "275") (name "unconnected-(IC3A-~{WE}-Pad16)") (class "Default")
      (node (ref "IC3") (pin "16") (pinfunction "~{WE}_16") (pintype "input"))
    )
    (net (code "276") (name "unconnected-(U$3-12V-PadA8)") (class "Default")
      (node (ref "U$3") (pin "A8") (pinfunction "12V_A8") (pintype "bidirectional"))
    )
    (net (code "277") (name "unconnected-(U$3-12V-PadB8)") (class "Default")
      (node (ref "U$3") (pin "B8") (pinfunction "12V_B8") (pintype "bidirectional"))
    )
    (net (code "278") (name "unconnected-(U$3-A1-PadA16)") (class "Default")
      (node (ref "U$3") (pin "A16") (pinfunction "A1_A16") (pintype "bidirectional"))
    )
    (net (code "279") (name "unconnected-(U$3-A2-PadA17)") (class "Default")
      (node (ref "U$3") (pin "A17") (pinfunction "A2_A17") (pintype "bidirectional"))
    )
    (net (code "280") (name "unconnected-(U$3-A3-PadA18)") (class "Default")
      (node (ref "U$3") (pin "A18") (pinfunction "A3_A18") (pintype "bidirectional"))
    )
    (net (code "281") (name "unconnected-(U$3-B0-PadB15)") (class "Default")
      (node (ref "U$3") (pin "B15") (pinfunction "B0_B15") (pintype "bidirectional"))
    )
    (net (code "282") (name "unconnected-(U$3-B1-PadB16)") (class "Default")
      (node (ref "U$3") (pin "B16") (pinfunction "B1_B16") (pintype "bidirectional"))
    )
    (net (code "283") (name "unconnected-(U$3-B2-PadB17)") (class "Default")
      (node (ref "U$3") (pin "B17") (pinfunction "B2_B17") (pintype "bidirectional"))
    )
    (net (code "284") (name "unconnected-(U$3-B3-PadB18)") (class "Default")
      (node (ref "U$3") (pin "B18") (pinfunction "B3_B18") (pintype "bidirectional"))
    )
    (net (code "285") (name "unconnected-(U$3-C0-PadA10)") (class "Default")
      (node (ref "U$3") (pin "A10") (pinfunction "C0_A10") (pintype "bidirectional"))
    )
    (net (code "286") (name "unconnected-(U$3-C1-PadA11)") (class "Default")
      (node (ref "U$3") (pin "A11") (pinfunction "C1_A11") (pintype "bidirectional"))
    )
    (net (code "287") (name "unconnected-(U$3-C2-PadA12)") (class "Default")
      (node (ref "U$3") (pin "A12") (pinfunction "C2_A12") (pintype "bidirectional"))
    )
    (net (code "288") (name "unconnected-(U$3-C3-PadA13)") (class "Default")
      (node (ref "U$3") (pin "A13") (pinfunction "C3_A13") (pintype "bidirectional"))
    )
    (net (code "289") (name "unconnected-(U$3-D0-PadB10)") (class "Default")
      (node (ref "U$3") (pin "B10") (pinfunction "D0_B10") (pintype "bidirectional"))
    )
    (net (code "290") (name "unconnected-(U$3-D1-PadB11)") (class "Default")
      (node (ref "U$3") (pin "B11") (pinfunction "D1_B11") (pintype "bidirectional"))
    )
    (net (code "291") (name "unconnected-(U$3-D2-PadB12)") (class "Default")
      (node (ref "U$3") (pin "B12") (pinfunction "D2_B12") (pintype "bidirectional"))
    )
    (net (code "292") (name "unconnected-(U$3-D3-PadB13)") (class "Default")
      (node (ref "U$3") (pin "B13") (pinfunction "D3_B13") (pintype "bidirectional"))
    )
    (net (code "293") (name "unconnected-(U$3-E0-PadA9)") (class "Default")
      (node (ref "U$3") (pin "A9") (pinfunction "E0_A9") (pintype "bidirectional"))
    )
    (net (code "294") (name "unconnected-(U$3-E1-PadB9)") (class "Default")
      (node (ref "U$3") (pin "B9") (pinfunction "E1_B9") (pintype "bidirectional"))
    )
    (net (code "295") (name "unconnected-(U$3-E2-PadA14)") (class "Default")
      (node (ref "U$3") (pin "A14") (pinfunction "E2_A14") (pintype "bidirectional"))
    )
    (net (code "296") (name "unconnected-(U$3-E3-PadB14)") (class "Default")
      (node (ref "U$3") (pin "B14") (pinfunction "E3_B14") (pintype "bidirectional"))
    )
    (net (code "297") (name "unconnected-(U$3-G0-PadB6)") (class "Default")
      (node (ref "U$3") (pin "B6") (pinfunction "G0_B6") (pintype "bidirectional"))
    )
    (net (code "298") (name "unconnected-(U$3-SCL-PadA5)") (class "Default")
      (node (ref "U$3") (pin "A5") (pinfunction "SCL_A5") (pintype "bidirectional"))
    )
    (net (code "299") (name "unconnected-(U$3-SDA-PadA6)") (class "Default")
      (node (ref "U$3") (pin "A6") (pinfunction "SDA_A6") (pintype "bidirectional"))
    )
    (net (code "300") (name "unconnected-(X2-Pad4)") (class "Default")
      (node (ref "X2") (pin "4") (pinfunction "4_4") (pintype "passive"))
    )
    (net (code "301") (name "unconnected-(X2-Pad9)") (class "Default")
      (node (ref "X2") (pin "9") (pinfunction "9_9") (pintype "passive"))
    )
    (net (code "302") (name "unconnected-(X2-Pad11)") (class "Default")
      (node (ref "X2") (pin "11") (pinfunction "11_11") (pintype "passive"))
    )
    (net (code "303") (name "unconnected-(X2-Pad12)") (class "Default")
      (node (ref "X2") (pin "12") (pinfunction "12_12") (pintype "passive"))
    )
    (net (code "304") (name "unconnected-(X2-Pad15)") (class "Default")
      (node (ref "X2") (pin "15") (pinfunction "15_15") (pintype "passive"))
    )
  )
)
